# 12S.net
KiCad netlist of a schematic drawn in EAGLE
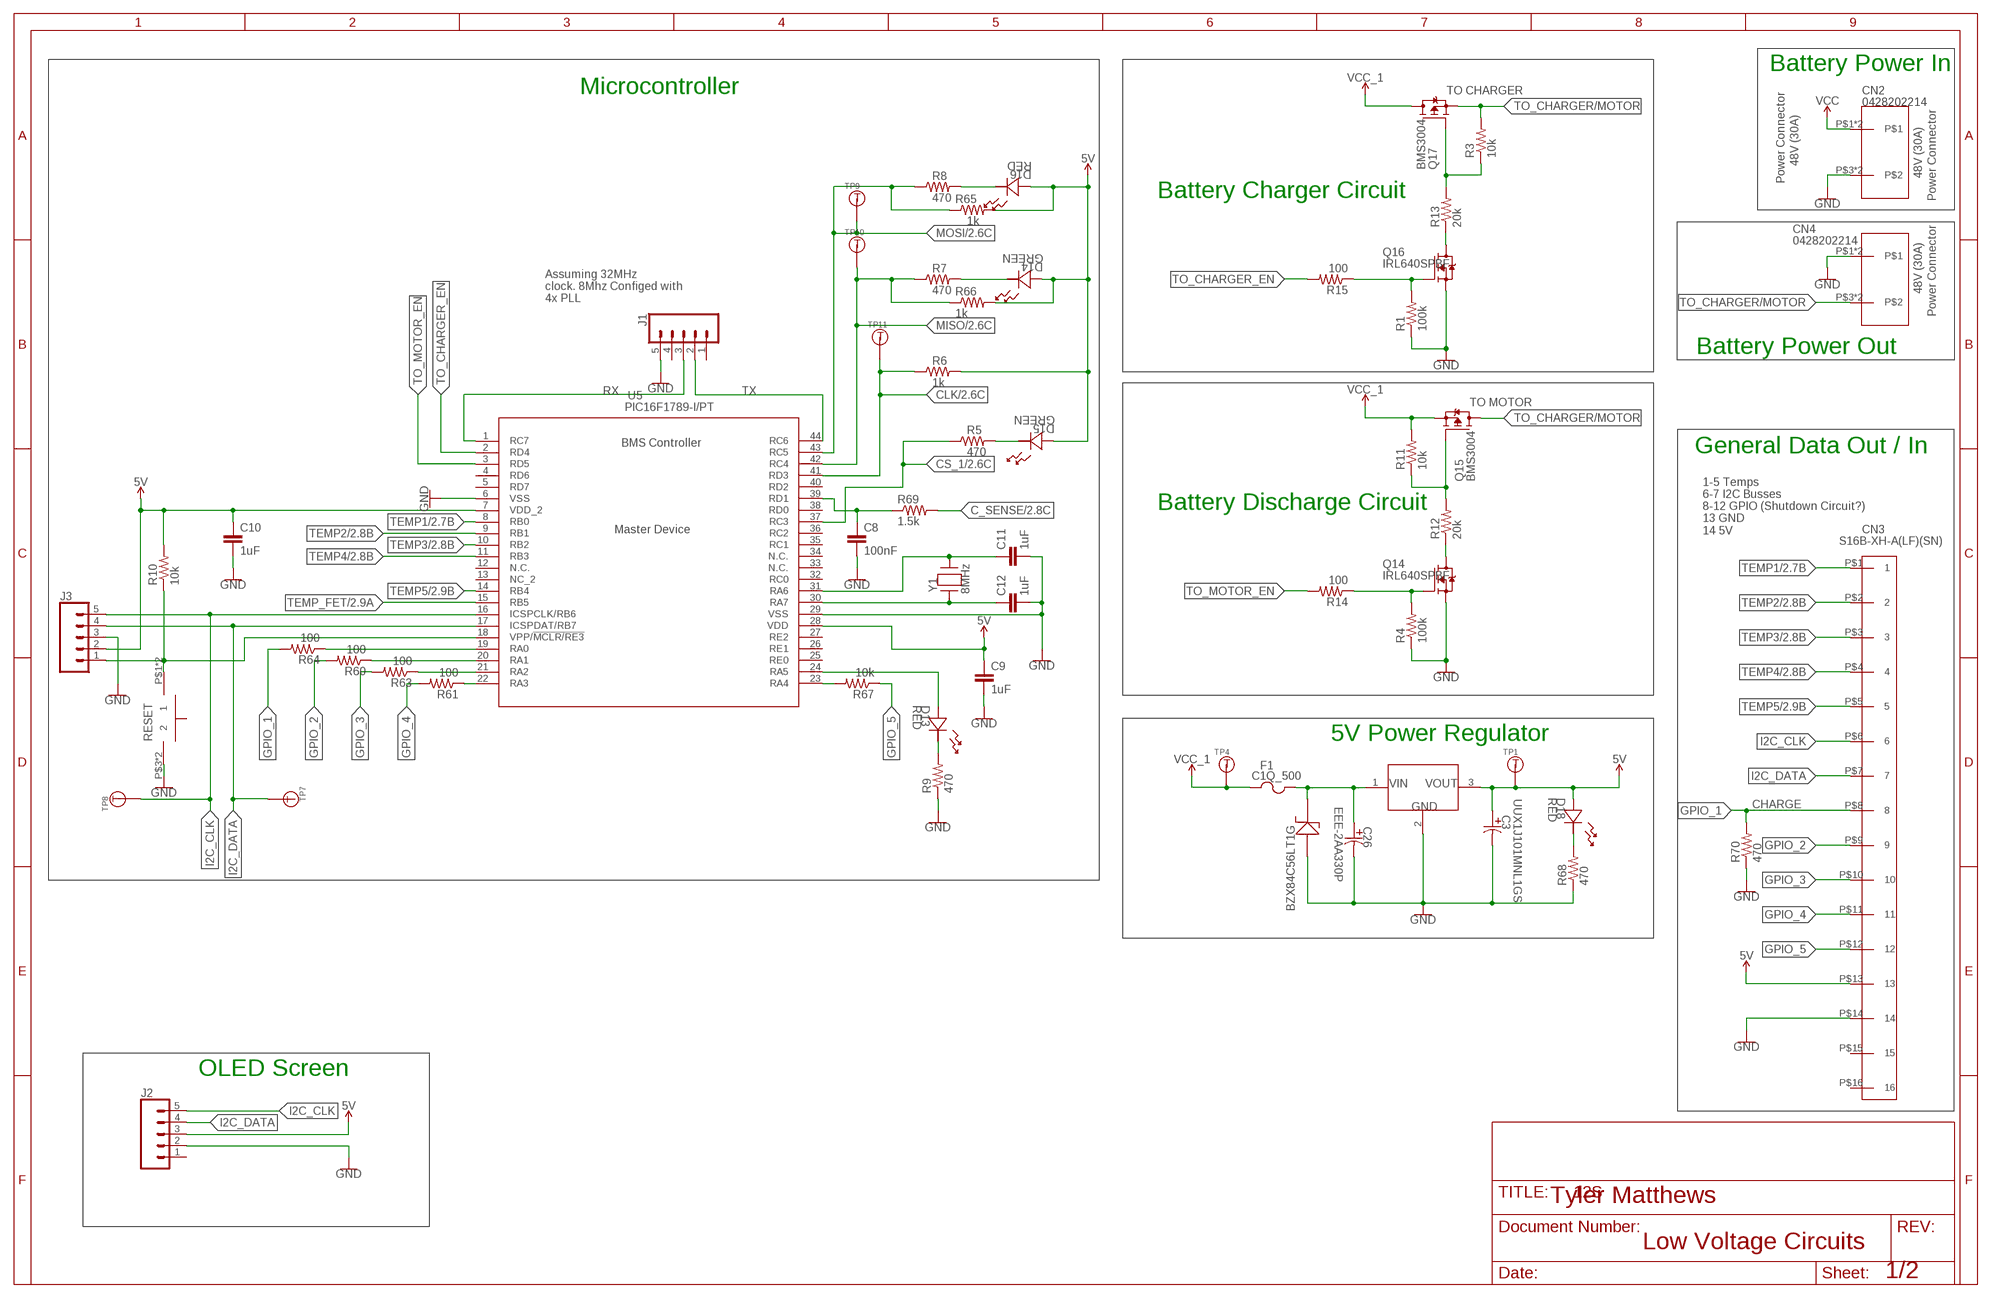
[diagram p0: schematic, sheet 1]
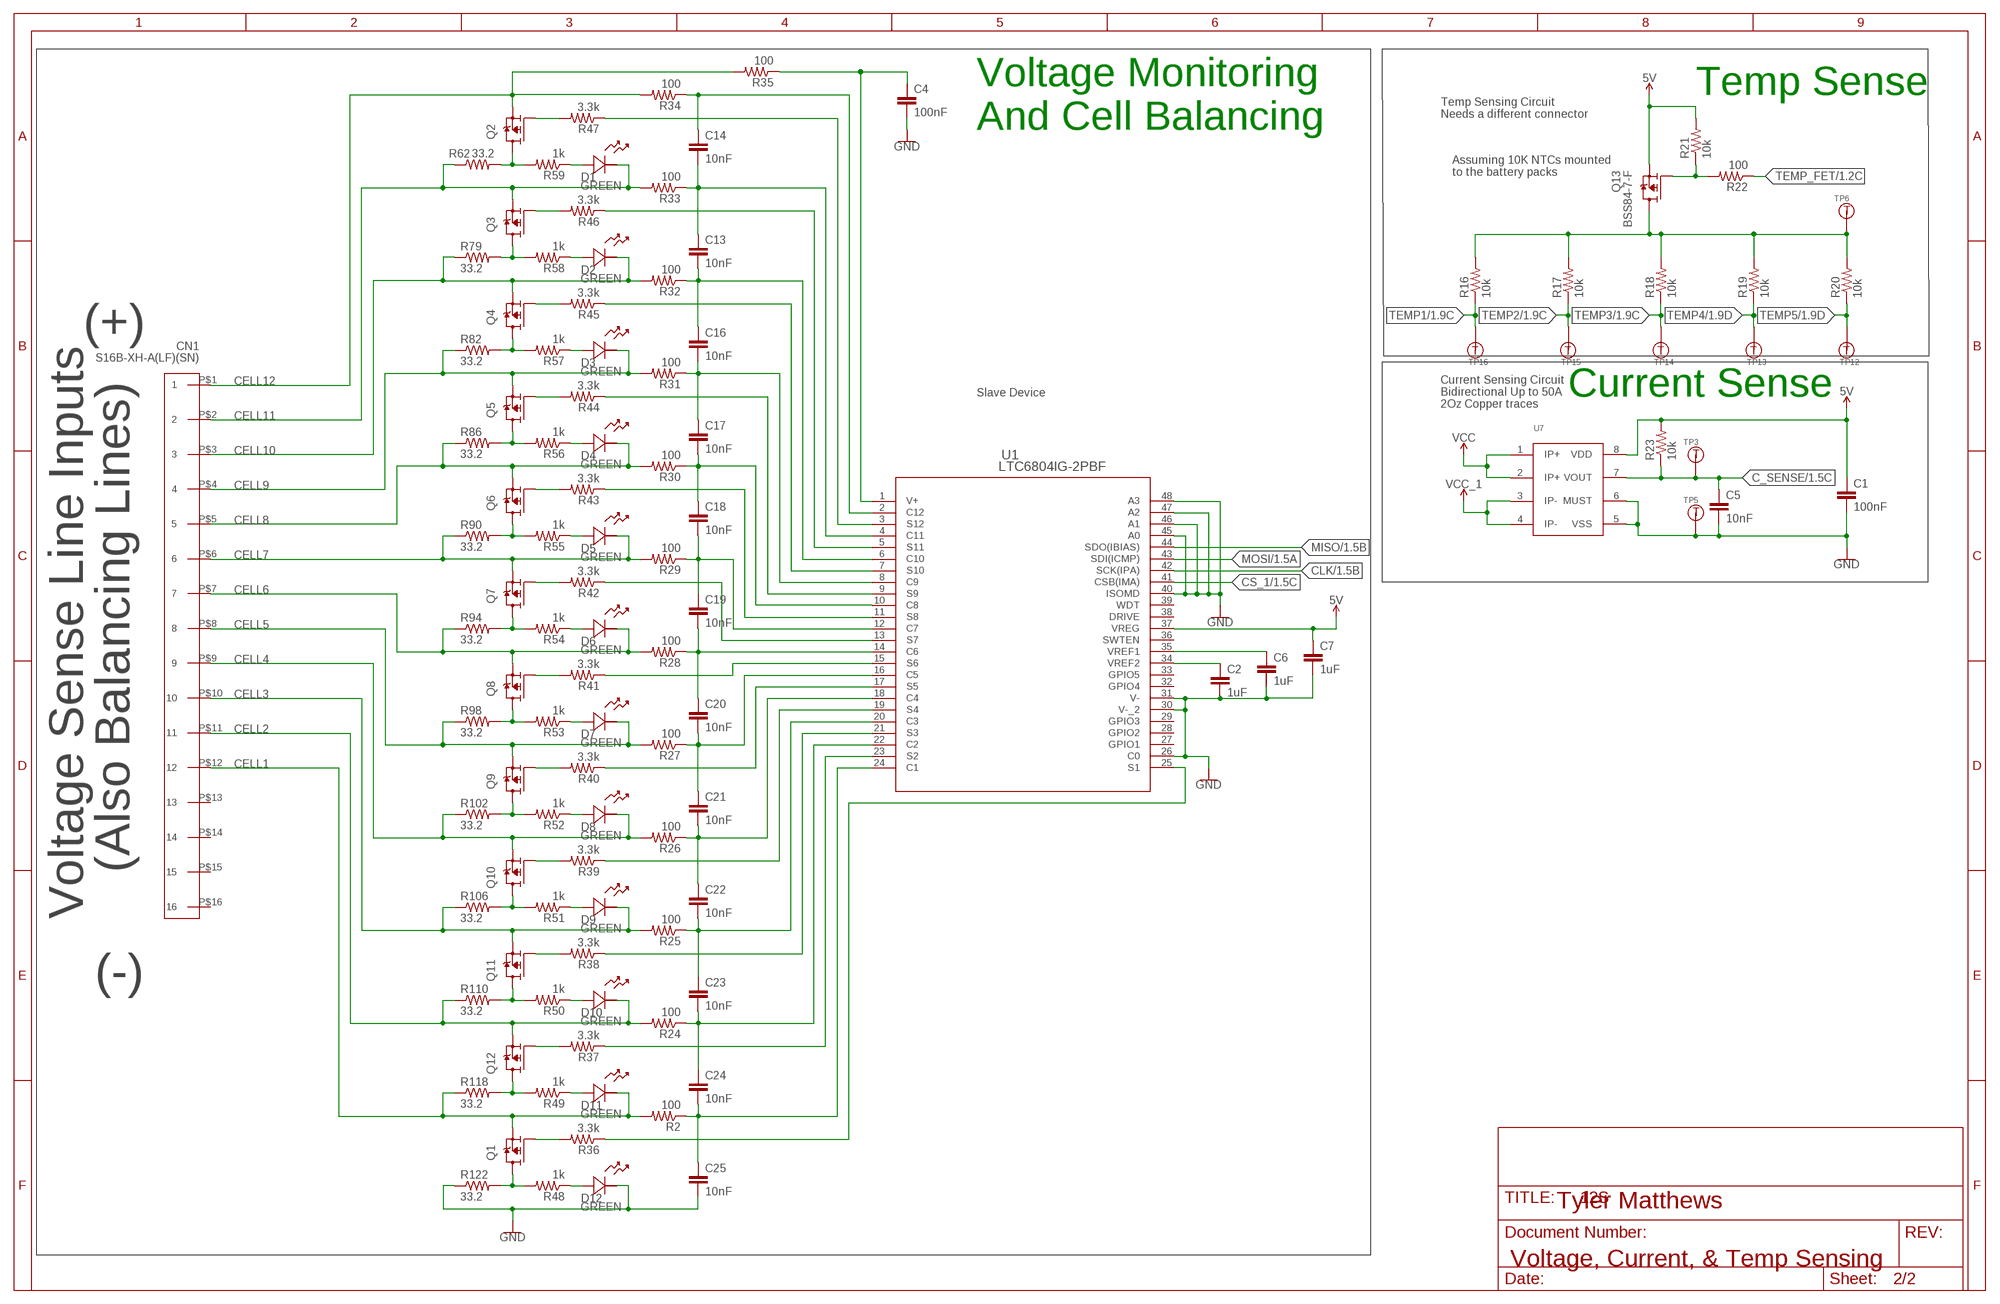
[diagram p1: schematic, sheet 2]

(export (version "E")
  (design (tool "Eeschema 10.0.6"))
  (components
    (comp (ref "C1")
      (value "100nF")
      (footprint "eagle-import:C0603")
      (libsource (lib "eagle-import") (part "C-EUC0603"))
    )
    (comp (ref "C2")
      (value "1uF")
      (footprint "eagle-import:C0603")
      (libsource (lib "eagle-import") (part "C-EUC0603"))
    )
    (comp (ref "C4")
      (value "100nF")
      (footprint "eagle-import:C0603")
      (libsource (lib "eagle-import") (part "C-EUC0603"))
    )
    (comp (ref "C5")
      (value "10nF")
      (footprint "eagle-import:C0603")
      (libsource (lib "eagle-import") (part "C-EUC0603"))
    )
    (comp (ref "C6")
      (value "1uF")
      (footprint "eagle-import:C0603")
      (libsource (lib "eagle-import") (part "C-EUC0603"))
    )
    (comp (ref "C7")
      (value "1uF")
      (footprint "eagle-import:C0603")
      (libsource (lib "eagle-import") (part "C-EUC0603"))
    )
    (comp (ref "C13")
      (value "10nF")
      (footprint "eagle-import:C0603")
      (libsource (lib "eagle-import") (part "C-EUC0603"))
    )
    (comp (ref "C14")
      (value "10nF")
      (footprint "eagle-import:C0603")
      (libsource (lib "eagle-import") (part "C-EUC0603"))
    )
    (comp (ref "C16")
      (value "10nF")
      (footprint "eagle-import:C0603")
      (libsource (lib "eagle-import") (part "C-EUC0603"))
    )
    (comp (ref "C17")
      (value "10nF")
      (footprint "eagle-import:C0603")
      (libsource (lib "eagle-import") (part "C-EUC0603"))
    )
    (comp (ref "C18")
      (value "10nF")
      (footprint "eagle-import:C0603")
      (libsource (lib "eagle-import") (part "C-EUC0603"))
    )
    (comp (ref "C19")
      (value "10nF")
      (footprint "eagle-import:C0603")
      (libsource (lib "eagle-import") (part "C-EUC0603"))
    )
    (comp (ref "C20")
      (value "10nF")
      (footprint "eagle-import:C0603")
      (libsource (lib "eagle-import") (part "C-EUC0603"))
    )
    (comp (ref "C21")
      (value "10nF")
      (footprint "eagle-import:C0603")
      (libsource (lib "eagle-import") (part "C-EUC0603"))
    )
    (comp (ref "C22")
      (value "10nF")
      (footprint "eagle-import:C0603")
      (libsource (lib "eagle-import") (part "C-EUC0603"))
    )
    (comp (ref "C23")
      (value "10nF")
      (footprint "eagle-import:C0603")
      (libsource (lib "eagle-import") (part "C-EUC0603"))
    )
    (comp (ref "C24")
      (value "10nF")
      (footprint "eagle-import:C0603")
      (libsource (lib "eagle-import") (part "C-EUC0603"))
    )
    (comp (ref "C25")
      (value "10nF")
      (footprint "eagle-import:C0603")
      (libsource (lib "eagle-import") (part "C-EUC0603"))
    )
    (comp (ref "CN1")
      (value "S16B-XH-A(LF)(SN)")
      (footprint "eagle-import:S16B-XH-A(LF)(SN)")
      (libsource (lib "eagle-import") (part "S16B-XH-A(LF)(SN)"))
    )
    (comp (ref "D1")
      (value "GREEN")
      (footprint "eagle-import:LED_DIALIGHT_598")
      (fields (field (name "MANUFACTURER_PART_NUMBER") "5988070107F"))
      (libsource (lib "eagle-import") (part "LED0603"))
    )
    (comp (ref "D2")
      (value "GREEN")
      (footprint "eagle-import:LED_DIALIGHT_598")
      (fields (field (name "MANUFACTURER_PART_NUMBER") "5988070107F"))
      (libsource (lib "eagle-import") (part "LED0603"))
    )
    (comp (ref "D3")
      (value "GREEN")
      (footprint "eagle-import:LED_DIALIGHT_598")
      (fields (field (name "MANUFACTURER_PART_NUMBER") "5988070107F"))
      (libsource (lib "eagle-import") (part "LED0603"))
    )
    (comp (ref "D4")
      (value "GREEN")
      (footprint "eagle-import:LED_DIALIGHT_598")
      (fields (field (name "MANUFACTURER_PART_NUMBER") "5988070107F"))
      (libsource (lib "eagle-import") (part "LED0603"))
    )
    (comp (ref "D5")
      (value "GREEN")
      (footprint "eagle-import:LED_DIALIGHT_598")
      (fields (field (name "MANUFACTURER_PART_NUMBER") "5988070107F"))
      (libsource (lib "eagle-import") (part "LED0603"))
    )
    (comp (ref "D6")
      (value "GREEN")
      (footprint "eagle-import:LED_DIALIGHT_598")
      (fields (field (name "MANUFACTURER_PART_NUMBER") "5988070107F"))
      (libsource (lib "eagle-import") (part "LED0603"))
    )
    (comp (ref "D7")
      (value "GREEN")
      (footprint "eagle-import:LED_DIALIGHT_598")
      (fields (field (name "MANUFACTURER_PART_NUMBER") "5988070107F"))
      (libsource (lib "eagle-import") (part "LED0603"))
    )
    (comp (ref "D8")
      (value "GREEN")
      (footprint "eagle-import:LED_DIALIGHT_598")
      (fields (field (name "MANUFACTURER_PART_NUMBER") "5988070107F"))
      (libsource (lib "eagle-import") (part "LED0603"))
    )
    (comp (ref "D9")
      (value "GREEN")
      (footprint "eagle-import:LED_DIALIGHT_598")
      (fields (field (name "MANUFACTURER_PART_NUMBER") "5988070107F"))
      (libsource (lib "eagle-import") (part "LED0603"))
    )
    (comp (ref "D10")
      (value "GREEN")
      (footprint "eagle-import:LED_DIALIGHT_598")
      (fields (field (name "MANUFACTURER_PART_NUMBER") "5988070107F"))
      (libsource (lib "eagle-import") (part "LED0603"))
    )
    (comp (ref "D11")
      (value "GREEN")
      (footprint "eagle-import:LED_DIALIGHT_598")
      (fields (field (name "MANUFACTURER_PART_NUMBER") "5988070107F"))
      (libsource (lib "eagle-import") (part "LED0603"))
    )
    (comp (ref "D12")
      (value "GREEN")
      (footprint "eagle-import:LED_DIALIGHT_598")
      (fields (field (name "MANUFACTURER_PART_NUMBER") "5988070107F"))
      (libsource (lib "eagle-import") (part "LED0603"))
    )
    (comp (ref "Q1")
      (value "BSS308PEH6327XTSA1")
      (footprint "eagle-import:BSS308PEH6327XTSA1")
      (libsource (lib "eagle-import") (part "BSS308PEH6327XTSA1"))
    )
    (comp (ref "Q2")
      (value "BSS308PEH6327XTSA1")
      (footprint "eagle-import:BSS308PEH6327XTSA1")
      (libsource (lib "eagle-import") (part "BSS308PEH6327XTSA1"))
    )
    (comp (ref "Q3")
      (value "BSS308PEH6327XTSA1")
      (footprint "eagle-import:BSS308PEH6327XTSA1")
      (libsource (lib "eagle-import") (part "BSS308PEH6327XTSA1"))
    )
    (comp (ref "Q4")
      (value "BSS308PEH6327XTSA1")
      (footprint "eagle-import:BSS308PEH6327XTSA1")
      (libsource (lib "eagle-import") (part "BSS308PEH6327XTSA1"))
    )
    (comp (ref "Q5")
      (value "BSS308PEH6327XTSA1")
      (footprint "eagle-import:BSS308PEH6327XTSA1")
      (libsource (lib "eagle-import") (part "BSS308PEH6327XTSA1"))
    )
    (comp (ref "Q6")
      (value "BSS308PEH6327XTSA1")
      (footprint "eagle-import:BSS308PEH6327XTSA1")
      (libsource (lib "eagle-import") (part "BSS308PEH6327XTSA1"))
    )
    (comp (ref "Q7")
      (value "BSS308PEH6327XTSA1")
      (footprint "eagle-import:BSS308PEH6327XTSA1")
      (libsource (lib "eagle-import") (part "BSS308PEH6327XTSA1"))
    )
    (comp (ref "Q8")
      (value "BSS308PEH6327XTSA1")
      (footprint "eagle-import:BSS308PEH6327XTSA1")
      (libsource (lib "eagle-import") (part "BSS308PEH6327XTSA1"))
    )
    (comp (ref "Q9")
      (value "BSS308PEH6327XTSA1")
      (footprint "eagle-import:BSS308PEH6327XTSA1")
      (libsource (lib "eagle-import") (part "BSS308PEH6327XTSA1"))
    )
    (comp (ref "Q10")
      (value "BSS308PEH6327XTSA1")
      (footprint "eagle-import:BSS308PEH6327XTSA1")
      (libsource (lib "eagle-import") (part "BSS308PEH6327XTSA1"))
    )
    (comp (ref "Q11")
      (value "BSS308PEH6327XTSA1")
      (footprint "eagle-import:BSS308PEH6327XTSA1")
      (libsource (lib "eagle-import") (part "BSS308PEH6327XTSA1"))
    )
    (comp (ref "Q12")
      (value "BSS308PEH6327XTSA1")
      (footprint "eagle-import:BSS308PEH6327XTSA1")
      (libsource (lib "eagle-import") (part "BSS308PEH6327XTSA1"))
    )
    (comp (ref "Q13")
      (value "BSS84-7-F")
      (footprint "eagle-import:SOT-23")
      (fields (field (name "MANUFACTURER_PART_NUMBER") "BSS847F"))
      (libsource (lib "eagle-import") (part "BSS84-7-F"))
    )
    (comp (ref "R2")
      (value "100")
      (footprint "eagle-import:R0603")
      (libsource (lib "eagle-import") (part "R-US_R0603"))
    )
    (comp (ref "R16")
      (value "10k")
      (footprint "eagle-import:R0603")
      (libsource (lib "eagle-import") (part "R-US_R0603"))
    )
    (comp (ref "R17")
      (value "10k")
      (footprint "eagle-import:R0603")
      (libsource (lib "eagle-import") (part "R-US_R0603"))
    )
    (comp (ref "R18")
      (value "10k")
      (footprint "eagle-import:R0603")
      (libsource (lib "eagle-import") (part "R-US_R0603"))
    )
    (comp (ref "R19")
      (value "10k")
      (footprint "eagle-import:R0603")
      (libsource (lib "eagle-import") (part "R-US_R0603"))
    )
    (comp (ref "R20")
      (value "10k")
      (footprint "eagle-import:R0603")
      (libsource (lib "eagle-import") (part "R-US_R0603"))
    )
    (comp (ref "R21")
      (value "10k")
      (footprint "eagle-import:R0603")
      (libsource (lib "eagle-import") (part "R-US_R0603"))
    )
    (comp (ref "R22")
      (value "100")
      (footprint "eagle-import:R0603")
      (libsource (lib "eagle-import") (part "R-US_R0603"))
    )
    (comp (ref "R23")
      (value "10k")
      (footprint "eagle-import:R0603")
      (libsource (lib "eagle-import") (part "R-US_R0603"))
    )
    (comp (ref "R24")
      (value "100")
      (footprint "eagle-import:R0603")
      (libsource (lib "eagle-import") (part "R-US_R0603"))
    )
    (comp (ref "R25")
      (value "100")
      (footprint "eagle-import:R0603")
      (libsource (lib "eagle-import") (part "R-US_R0603"))
    )
    (comp (ref "R26")
      (value "100")
      (footprint "eagle-import:R0603")
      (libsource (lib "eagle-import") (part "R-US_R0603"))
    )
    (comp (ref "R27")
      (value "100")
      (footprint "eagle-import:R0603")
      (libsource (lib "eagle-import") (part "R-US_R0603"))
    )
    (comp (ref "R28")
      (value "100")
      (footprint "eagle-import:R0603")
      (libsource (lib "eagle-import") (part "R-US_R0603"))
    )
    (comp (ref "R29")
      (value "100")
      (footprint "eagle-import:R0603")
      (libsource (lib "eagle-import") (part "R-US_R0603"))
    )
    (comp (ref "R30")
      (value "100")
      (footprint "eagle-import:R0603")
      (libsource (lib "eagle-import") (part "R-US_R0603"))
    )
    (comp (ref "R31")
      (value "100")
      (footprint "eagle-import:R0603")
      (libsource (lib "eagle-import") (part "R-US_R0603"))
    )
    (comp (ref "R32")
      (value "100")
      (footprint "eagle-import:R0603")
      (libsource (lib "eagle-import") (part "R-US_R0603"))
    )
    (comp (ref "R33")
      (value "100")
      (footprint "eagle-import:R0603")
      (libsource (lib "eagle-import") (part "R-US_R0603"))
    )
    (comp (ref "R34")
      (value "100")
      (footprint "eagle-import:R0603")
      (libsource (lib "eagle-import") (part "R-US_R0603"))
    )
    (comp (ref "R35")
      (value "100")
      (footprint "eagle-import:R0603")
      (libsource (lib "eagle-import") (part "R-US_R0603"))
    )
    (comp (ref "R36")
      (value "3.3k")
      (footprint "eagle-import:R0603")
      (libsource (lib "eagle-import") (part "R-US_R0603"))
    )
    (comp (ref "R37")
      (value "3.3k")
      (footprint "eagle-import:R0603")
      (libsource (lib "eagle-import") (part "R-US_R0603"))
    )
    (comp (ref "R38")
      (value "3.3k")
      (footprint "eagle-import:R0603")
      (libsource (lib "eagle-import") (part "R-US_R0603"))
    )
    (comp (ref "R39")
      (value "3.3k")
      (footprint "eagle-import:R0603")
      (libsource (lib "eagle-import") (part "R-US_R0603"))
    )
    (comp (ref "R40")
      (value "3.3k")
      (footprint "eagle-import:R0603")
      (libsource (lib "eagle-import") (part "R-US_R0603"))
    )
    (comp (ref "R41")
      (value "3.3k")
      (footprint "eagle-import:R0603")
      (libsource (lib "eagle-import") (part "R-US_R0603"))
    )
    (comp (ref "R42")
      (value "3.3k")
      (footprint "eagle-import:R0603")
      (libsource (lib "eagle-import") (part "R-US_R0603"))
    )
    (comp (ref "R43")
      (value "3.3k")
      (footprint "eagle-import:R0603")
      (libsource (lib "eagle-import") (part "R-US_R0603"))
    )
    (comp (ref "R44")
      (value "3.3k")
      (footprint "eagle-import:R0603")
      (libsource (lib "eagle-import") (part "R-US_R0603"))
    )
    (comp (ref "R45")
      (value "3.3k")
      (footprint "eagle-import:R0603")
      (libsource (lib "eagle-import") (part "R-US_R0603"))
    )
    (comp (ref "R46")
      (value "3.3k")
      (footprint "eagle-import:R0603")
      (libsource (lib "eagle-import") (part "R-US_R0603"))
    )
    (comp (ref "R47")
      (value "3.3k")
      (footprint "eagle-import:R0603")
      (libsource (lib "eagle-import") (part "R-US_R0603"))
    )
    (comp (ref "R48")
      (value "1k")
      (footprint "eagle-import:R0603")
      (libsource (lib "eagle-import") (part "R-US_R0603"))
    )
    (comp (ref "R49")
      (value "1k")
      (footprint "eagle-import:R0603")
      (libsource (lib "eagle-import") (part "R-US_R0603"))
    )
    (comp (ref "R50")
      (value "1k")
      (footprint "eagle-import:R0603")
      (libsource (lib "eagle-import") (part "R-US_R0603"))
    )
    (comp (ref "R51")
      (value "1k")
      (footprint "eagle-import:R0603")
      (libsource (lib "eagle-import") (part "R-US_R0603"))
    )
    (comp (ref "R52")
      (value "1k")
      (footprint "eagle-import:R0603")
      (libsource (lib "eagle-import") (part "R-US_R0603"))
    )
    (comp (ref "R53")
      (value "1k")
      (footprint "eagle-import:R0603")
      (libsource (lib "eagle-import") (part "R-US_R0603"))
    )
    (comp (ref "R54")
      (value "1k")
      (footprint "eagle-import:R0603")
      (libsource (lib "eagle-import") (part "R-US_R0603"))
    )
    (comp (ref "R55")
      (value "1k")
      (footprint "eagle-import:R0603")
      (libsource (lib "eagle-import") (part "R-US_R0603"))
    )
    (comp (ref "R56")
      (value "1k")
      (footprint "eagle-import:R0603")
      (libsource (lib "eagle-import") (part "R-US_R0603"))
    )
    (comp (ref "R57")
      (value "1k")
      (footprint "eagle-import:R0603")
      (libsource (lib "eagle-import") (part "R-US_R0603"))
    )
    (comp (ref "R58")
      (value "1k")
      (footprint "eagle-import:R0603")
      (libsource (lib "eagle-import") (part "R-US_R0603"))
    )
    (comp (ref "R59")
      (value "1k")
      (footprint "eagle-import:R0603")
      (libsource (lib "eagle-import") (part "R-US_R0603"))
    )
    (comp (ref "R62")
      (value "33.2")
      (footprint "eagle-import:R0805")
      (libsource (lib "eagle-import") (part "R-US_R0805"))
    )
    (comp (ref "R79")
      (value "33.2")
      (footprint "eagle-import:R0805")
      (libsource (lib "eagle-import") (part "R-US_R0805"))
    )
    (comp (ref "R82")
      (value "33.2")
      (footprint "eagle-import:R0805")
      (libsource (lib "eagle-import") (part "R-US_R0805"))
    )
    (comp (ref "R86")
      (value "33.2")
      (footprint "eagle-import:R0805")
      (libsource (lib "eagle-import") (part "R-US_R0805"))
    )
    (comp (ref "R90")
      (value "33.2")
      (footprint "eagle-import:R0805")
      (libsource (lib "eagle-import") (part "R-US_R0805"))
    )
    (comp (ref "R94")
      (value "33.2")
      (footprint "eagle-import:R0805")
      (libsource (lib "eagle-import") (part "R-US_R0805"))
    )
    (comp (ref "R98")
      (value "33.2")
      (footprint "eagle-import:R0805")
      (libsource (lib "eagle-import") (part "R-US_R0805"))
    )
    (comp (ref "R102")
      (value "33.2")
      (footprint "eagle-import:R0805")
      (libsource (lib "eagle-import") (part "R-US_R0805"))
    )
    (comp (ref "R106")
      (value "33.2")
      (footprint "eagle-import:R0805")
      (libsource (lib "eagle-import") (part "R-US_R0805"))
    )
    (comp (ref "R110")
      (value "33.2")
      (footprint "eagle-import:R0805")
      (libsource (lib "eagle-import") (part "R-US_R0805"))
    )
    (comp (ref "R118")
      (value "33.2")
      (footprint "eagle-import:R0805")
      (libsource (lib "eagle-import") (part "R-US_R0805"))
    )
    (comp (ref "R122")
      (value "33.2")
      (footprint "eagle-import:R0805")
      (libsource (lib "eagle-import") (part "R-US_R0805"))
    )
    (comp (ref "TP3")
      (value "TP5015")
      (footprint "eagle-import:TP5015")
      (fields (field (name "MANUFACTURER_PART_NUMBER") "5015"))
      (libsource (lib "eagle-import") (part "TP5015"))
    )
    (comp (ref "TP5")
      (value "TP5015")
      (footprint "eagle-import:TP5015")
      (fields (field (name "MANUFACTURER_PART_NUMBER") "5015"))
      (libsource (lib "eagle-import") (part "TP5015"))
    )
    (comp (ref "TP6")
      (value "TP5015")
      (footprint "eagle-import:TP5015")
      (fields (field (name "MANUFACTURER_PART_NUMBER") "5015"))
      (libsource (lib "eagle-import") (part "TP5015"))
    )
    (comp (ref "TP12")
      (value "TP5015")
      (footprint "eagle-import:TP5015")
      (fields (field (name "MANUFACTURER_PART_NUMBER") "5015"))
      (libsource (lib "eagle-import") (part "TP5015"))
    )
    (comp (ref "TP13")
      (value "TP5015")
      (footprint "eagle-import:TP5015")
      (fields (field (name "MANUFACTURER_PART_NUMBER") "5015"))
      (libsource (lib "eagle-import") (part "TP5015"))
    )
    (comp (ref "TP14")
      (value "TP5015")
      (footprint "eagle-import:TP5015")
      (fields (field (name "MANUFACTURER_PART_NUMBER") "5015"))
      (libsource (lib "eagle-import") (part "TP5015"))
    )
    (comp (ref "TP15")
      (value "TP5015")
      (footprint "eagle-import:TP5015")
      (fields (field (name "MANUFACTURER_PART_NUMBER") "5015"))
      (libsource (lib "eagle-import") (part "TP5015"))
    )
    (comp (ref "TP16")
      (value "TP5015")
      (footprint "eagle-import:TP5015")
      (fields (field (name "MANUFACTURER_PART_NUMBER") "5015"))
      (libsource (lib "eagle-import") (part "TP5015"))
    )
    (comp (ref "U1")
      (value "LTC6804IG-2PBF")
      (footprint "eagle-import:SSOP-48_G")
      (fields (field (name "MANUFACTURER_PART_NUMBER") "LTC6804HG-2#PBF"))
      (libsource (lib "eagle-import") (part "LTC6804IG-2PBF"))
    )
    (comp (ref "U7")
      (value "MLX91210")
      (footprint "eagle-import:SOIC-8")
      (fields (field (name "MANUFACTURER_PART_NUMBER") "MLX91210KDC-CAS-102-SP"))
      (libsource (lib "eagle-import") (part "MLX91210"))
    )
    (comp (ref "C3")
      (value "UUX1J101MNL1GS")
      (footprint "eagle-import:PCAP_10X10-ELECT")
      (libsource (lib "eagle-import") (part "UUX1J101MNL1GS"))
    )
    (comp (ref "C8")
      (value "100nF")
      (footprint "eagle-import:C0603")
      (libsource (lib "eagle-import") (part "C-EUC0603"))
    )
    (comp (ref "C9")
      (value "1uF")
      (footprint "eagle-import:C0603")
      (libsource (lib "eagle-import") (part "C-EUC0603"))
    )
    (comp (ref "C10")
      (value "1uF")
      (footprint "eagle-import:C0603")
      (libsource (lib "eagle-import") (part "C-EUC0603"))
    )
    (comp (ref "C11")
      (value "1uF")
      (footprint "eagle-import:C0603")
      (libsource (lib "eagle-import") (part "C-EUC0603"))
    )
    (comp (ref "C12")
      (value "1uF")
      (footprint "eagle-import:C0603")
      (libsource (lib "eagle-import") (part "C-EUC0603"))
    )
    (comp (ref "C26")
      (value "EEE-2AA330P")
      (footprint "eagle-import:CAP_EEE_G")
      (fields (field (name "MANUFACTURER_PART_NUMBER") "EEE2AA330P"))
      (libsource (lib "eagle-import") (part "EEE-2AA330P"))
    )
    (comp (ref "CN2")
      (value "0428202214")
      (footprint "eagle-import:0428202214")
      (libsource (lib "eagle-import") (part "0428202214"))
    )
    (comp (ref "CN3")
      (value "S16B-XH-A(LF)(SN)")
      (footprint "eagle-import:S16B-XH-A(LF)(SN)")
      (libsource (lib "eagle-import") (part "S16B-XH-A(LF)(SN)"))
    )
    (comp (ref "CN4")
      (value "0428202214")
      (footprint "eagle-import:0428202214")
      (libsource (lib "eagle-import") (part "0428202214"))
    )
    (comp (ref "D13")
      (value "RED")
      (footprint "eagle-import:LED_DIALIGHT_598")
      (fields (field (name "MANUFACTURER_PART_NUMBER") "5988070107F"))
      (libsource (lib "eagle-import") (part "LED0603"))
    )
    (comp (ref "D14")
      (value "GREEN")
      (footprint "eagle-import:LED_DIALIGHT_598")
      (fields (field (name "MANUFACTURER_PART_NUMBER") "5988070107F"))
      (libsource (lib "eagle-import") (part "LED0603"))
    )
    (comp (ref "D15")
      (value "GREEN")
      (footprint "eagle-import:LED_DIALIGHT_598")
      (fields (field (name "MANUFACTURER_PART_NUMBER") "5988070107F"))
      (libsource (lib "eagle-import") (part "LED0603"))
    )
    (comp (ref "D16")
      (value "RED")
      (footprint "eagle-import:LED_DIALIGHT_598")
      (fields (field (name "MANUFACTURER_PART_NUMBER") "5988070107F"))
      (libsource (lib "eagle-import") (part "LED0603"))
    )
    (comp (ref "D17")
      (value "BZX84C56LT1G")
      (footprint "eagle-import:SOT-23")
      (libsource (lib "eagle-import") (part "BZX84C56LT1G"))
    )
    (comp (ref "D18")
      (value "RED")
      (footprint "eagle-import:LED_DIALIGHT_598")
      (fields (field (name "MANUFACTURER_PART_NUMBER") "5988070107F"))
      (libsource (lib "eagle-import") (part "LED0603"))
    )
    (comp (ref "F1")
      (value "C1Q_500")
      (footprint "eagle-import:C1")
      (fields (field (name "MANUFACTURER_PART_NUMBER") "C1Q 500"))
      (libsource (lib "eagle-import") (part "C1Q_500"))
    )
    (comp (ref "J1")
      (value "CONN_05")
      (footprint "eagle-import:1X05")
      (fields (field (name "MANUFACTURER_PART_NUMBER") "M20-9990546"))
      (libsource (lib "eagle-import") (part "CONN_05"))
    )
    (comp (ref "J2")
      (value "CONN_05")
      (footprint "eagle-import:1X05")
      (fields (field (name "MANUFACTURER_PART_NUMBER") "M20-9990546"))
      (libsource (lib "eagle-import") (part "CONN_05"))
    )
    (comp (ref "J3")
      (value "CONN_05")
      (footprint "eagle-import:1X05")
      (fields (field (name "MANUFACTURER_PART_NUMBER") "M20-9990546"))
      (libsource (lib "eagle-import") (part "CONN_05"))
    )
    (comp (ref "Q14")
      (value "IRL640SPBF")
      (footprint "eagle-import:D2PAK")
      (libsource (lib "eagle-import") (part "IRL640SPBF"))
    )
    (comp (ref "Q15")
      (value "BMS3004")
      (footprint "eagle-import:TO-220")
      (fields (field (name "MANUFACTURER_PART_NUMBER") "BMS3004-1E"))
      (libsource (lib "eagle-import") (part "BMS3004"))
    )
    (comp (ref "Q16")
      (value "IRL640SPBF")
      (footprint "eagle-import:D2PAK")
      (libsource (lib "eagle-import") (part "IRL640SPBF"))
    )
    (comp (ref "Q17")
      (value "BMS3004")
      (footprint "eagle-import:TO-220")
      (fields (field (name "MANUFACTURER_PART_NUMBER") "BMS3004-1E"))
      (libsource (lib "eagle-import") (part "BMS3004"))
    )
    (comp (ref "R1")
      (value "100k")
      (footprint "eagle-import:R0603")
      (libsource (lib "eagle-import") (part "R-US_R0603"))
    )
    (comp (ref "R3")
      (value "10k")
      (footprint "eagle-import:R0603")
      (libsource (lib "eagle-import") (part "R-US_R0603"))
    )
    (comp (ref "R4")
      (value "100k")
      (footprint "eagle-import:R0603")
      (libsource (lib "eagle-import") (part "R-US_R0603"))
    )
    (comp (ref "R5")
      (value "470")
      (footprint "eagle-import:R0603")
      (libsource (lib "eagle-import") (part "R-US_R0603"))
    )
    (comp (ref "R6")
      (value "1k")
      (footprint "eagle-import:R0603")
      (libsource (lib "eagle-import") (part "R-US_R0603"))
    )
    (comp (ref "R7")
      (value "470")
      (footprint "eagle-import:R0603")
      (libsource (lib "eagle-import") (part "R-US_R0603"))
    )
    (comp (ref "R8")
      (value "470")
      (footprint "eagle-import:R0603")
      (libsource (lib "eagle-import") (part "R-US_R0603"))
    )
    (comp (ref "R9")
      (value "470")
      (footprint "eagle-import:R0603")
      (libsource (lib "eagle-import") (part "R-US_R0603"))
    )
    (comp (ref "R10")
      (value "10k")
      (footprint "eagle-import:R0603")
      (libsource (lib "eagle-import") (part "R-US_R0603"))
    )
    (comp (ref "R11")
      (value "10k")
      (footprint "eagle-import:R0603")
      (libsource (lib "eagle-import") (part "R-US_R0603"))
    )
    (comp (ref "R12")
      (value "20k")
      (footprint "eagle-import:R0603")
      (libsource (lib "eagle-import") (part "R-US_R0603"))
    )
    (comp (ref "R13")
      (value "20k")
      (footprint "eagle-import:R0603")
      (libsource (lib "eagle-import") (part "R-US_R0603"))
    )
    (comp (ref "R14")
      (value "100")
      (footprint "eagle-import:R0603")
      (libsource (lib "eagle-import") (part "R-US_R0603"))
    )
    (comp (ref "R15")
      (value "100")
      (footprint "eagle-import:R0603")
      (libsource (lib "eagle-import") (part "R-US_R0603"))
    )
    (comp (ref "R60")
      (value "100")
      (footprint "eagle-import:R0603")
      (libsource (lib "eagle-import") (part "R-US_R0603"))
    )
    (comp (ref "R61")
      (value "100")
      (footprint "eagle-import:R0603")
      (libsource (lib "eagle-import") (part "R-US_R0603"))
    )
    (comp (ref "R63")
      (value "100")
      (footprint "eagle-import:R0603")
      (libsource (lib "eagle-import") (part "R-US_R0603"))
    )
    (comp (ref "R64")
      (value "100")
      (footprint "eagle-import:R0603")
      (libsource (lib "eagle-import") (part "R-US_R0603"))
    )
    (comp (ref "R65")
      (value "1k")
      (footprint "eagle-import:R0603")
      (libsource (lib "eagle-import") (part "R-US_R0603"))
    )
    (comp (ref "R66")
      (value "1k")
      (footprint "eagle-import:R0603")
      (libsource (lib "eagle-import") (part "R-US_R0603"))
    )
    (comp (ref "R67")
      (value "10k")
      (footprint "eagle-import:R0603")
      (libsource (lib "eagle-import") (part "R-US_R0603"))
    )
    (comp (ref "R68")
      (value "470")
      (footprint "eagle-import:R0603")
      (libsource (lib "eagle-import") (part "R-US_R0603"))
    )
    (comp (ref "R69")
      (value "1.5k")
      (footprint "eagle-import:R0603")
      (libsource (lib "eagle-import") (part "R-US_R0603"))
    )
    (comp (ref "R70")
      (value "470")
      (footprint "eagle-import:R0603")
      (libsource (lib "eagle-import") (part "R-US_R0603"))
    )
    (comp (ref "S2")
      (value "TL3305AF260QG")
      (footprint "eagle-import:TL3305AF260QG")
      (libsource (lib "eagle-import") (part "TL3305AF260QG"))
    )
    (comp (ref "TP1")
      (value "TP5015")
      (footprint "eagle-import:TP5015")
      (fields (field (name "MANUFACTURER_PART_NUMBER") "5015"))
      (libsource (lib "eagle-import") (part "TP5015"))
    )
    (comp (ref "TP4")
      (value "TP5015")
      (footprint "eagle-import:TP5015")
      (fields (field (name "MANUFACTURER_PART_NUMBER") "5015"))
      (libsource (lib "eagle-import") (part "TP5015"))
    )
    (comp (ref "TP7")
      (value "TP5015")
      (footprint "eagle-import:TP5015")
      (fields (field (name "MANUFACTURER_PART_NUMBER") "5015"))
      (libsource (lib "eagle-import") (part "TP5015"))
    )
    (comp (ref "TP8")
      (value "TP5015")
      (footprint "eagle-import:TP5015")
      (fields (field (name "MANUFACTURER_PART_NUMBER") "5015"))
      (libsource (lib "eagle-import") (part "TP5015"))
    )
    (comp (ref "TP9")
      (value "TP5015")
      (footprint "eagle-import:TP5015")
      (fields (field (name "MANUFACTURER_PART_NUMBER") "5015"))
      (libsource (lib "eagle-import") (part "TP5015"))
    )
    (comp (ref "TP10")
      (value "TP5015")
      (footprint "eagle-import:TP5015")
      (fields (field (name "MANUFACTURER_PART_NUMBER") "5015"))
      (libsource (lib "eagle-import") (part "TP5015"))
    )
    (comp (ref "TP11")
      (value "TP5015")
      (footprint "eagle-import:TP5015")
      (fields (field (name "MANUFACTURER_PART_NUMBER") "5015"))
      (libsource (lib "eagle-import") (part "TP5015"))
    )
    (comp (ref "U3")
      (value "SRH05S05")
      (footprint "eagle-import:SIP3")
      (libsource (lib "eagle-import") (part "SRH05S05"))
    )
    (comp (ref "U5")
      (value "PIC16F1789-I/PT")
      (footprint "eagle-import:TQFP44_MC")
      (fields (field (name "MANUFACTURER_PART_NUMBER") "PIC16F1789T-I/PT"))
      (libsource (lib "eagle-import") (part "PIC16F1789-I/PT"))
    )
    (comp (ref "Y1")
      (value "8MHz")
      (footprint "eagle-import:CRYSTAL_HC49SDLF")
      (fields (field (name "MANUFACTURER_PART_NUMBER") "FC4SDCBMF8.0-T1"))
      (libsource (lib "eagle-import") (part "FOXSDLF/080-20"))
    )
  )
  (nets
    (net (code "1") (name "5V") (class "Default")
      (node (ref "C1") (pin "1") (pinfunction "1_1") (pintype "passive"))
      (node (ref "C10") (pin "1") (pinfunction "1_1") (pintype "passive"))
      (node (ref "C3") (pin "1") (pinfunction "11_1") (pintype "passive"))
      (node (ref "C7") (pin "1") (pinfunction "1_1") (pintype "passive"))
      (node (ref "C9") (pin "1") (pinfunction "1_1") (pintype "passive"))
      (node (ref "CN3") (pin "P$13") (pinfunction "13_P$13") (pintype "bidirectional"))
      (node (ref "D14") (pin "2") (pinfunction "22_2") (pintype "passive"))
      (node (ref "D15") (pin "2") (pinfunction "22_2") (pintype "passive"))
      (node (ref "D16") (pin "2") (pinfunction "22_2") (pintype "passive"))
      (node (ref "D18") (pin "2") (pinfunction "22_2") (pintype "passive"))
      (node (ref "J2") (pin "3") (pinfunction "3_3") (pintype "passive"))
      (node (ref "J3") (pin "2") (pinfunction "2_2") (pintype "passive"))
      (node (ref "Q13") (pin "2") (pinfunction "S_2") (pintype "passive"))
      (node (ref "R10") (pin "2") (pinfunction "2_2") (pintype "passive"))
      (node (ref "R21") (pin "2") (pinfunction "2_2") (pintype "passive"))
      (node (ref "R23") (pin "2") (pinfunction "2_2") (pintype "passive"))
      (node (ref "R6") (pin "2") (pinfunction "2_2") (pintype "passive"))
      (node (ref "R65") (pin "2") (pinfunction "2_2") (pintype "passive"))
      (node (ref "R66") (pin "2") (pinfunction "2_2") (pintype "passive"))
      (node (ref "TP1") (pin "P$1") (pinfunction "P$1_P$1") (pintype "bidirectional"))
      (node (ref "U1") (pin "37") (pinfunction "VREG_37") (pintype "passive"))
      (node (ref "U3") (pin "3") (pinfunction "VOUT_3") (pintype "bidirectional"))
      (node (ref "U5") (pin "28") (pinfunction "VDD_28") (pintype "power_in"))
      (node (ref "U5") (pin "7") (pinfunction "VDD_2_7") (pintype "power_in"))
      (node (ref "U7") (pin "8") (pinfunction "VDD_8") (pintype "bidirectional"))
    )
    (net (code "2") (name "CELL1") (class "Default")
      (node (ref "CN1") (pin "P$12") (pinfunction "12_P$12") (pintype "bidirectional"))
      (node (ref "D11") (pin "1") (pinfunction "11_1") (pintype "passive"))
      (node (ref "Q1") (pin "P$S") (pinfunction "S_P$S") (pintype "passive"))
      (node (ref "R118") (pin "1") (pinfunction "1_1") (pintype "passive"))
      (node (ref "R2") (pin "2") (pinfunction "2_2") (pintype "passive"))
    )
    (net (code "3") (name "CELL2") (class "Default")
      (node (ref "CN1") (pin "P$11") (pinfunction "11_P$11") (pintype "bidirectional"))
      (node (ref "D10") (pin "1") (pinfunction "11_1") (pintype "passive"))
      (node (ref "Q12") (pin "P$S") (pinfunction "S_P$S") (pintype "passive"))
      (node (ref "R110") (pin "1") (pinfunction "1_1") (pintype "passive"))
      (node (ref "R24") (pin "2") (pinfunction "2_2") (pintype "passive"))
    )
    (net (code "4") (name "CELL3") (class "Default")
      (node (ref "CN1") (pin "P$10") (pinfunction "10_P$10") (pintype "bidirectional"))
      (node (ref "D9") (pin "1") (pinfunction "11_1") (pintype "passive"))
      (node (ref "Q11") (pin "P$S") (pinfunction "S_P$S") (pintype "passive"))
      (node (ref "R106") (pin "1") (pinfunction "1_1") (pintype "passive"))
      (node (ref "R25") (pin "2") (pinfunction "2_2") (pintype "passive"))
    )
    (net (code "5") (name "CELL4") (class "Default")
      (node (ref "CN1") (pin "P$9") (pinfunction "9_P$9") (pintype "bidirectional"))
      (node (ref "D8") (pin "1") (pinfunction "11_1") (pintype "passive"))
      (node (ref "Q10") (pin "P$S") (pinfunction "S_P$S") (pintype "passive"))
      (node (ref "R102") (pin "1") (pinfunction "1_1") (pintype "passive"))
      (node (ref "R26") (pin "2") (pinfunction "2_2") (pintype "passive"))
    )
    (net (code "6") (name "CELL5") (class "Default")
      (node (ref "CN1") (pin "P$8") (pinfunction "8_P$8") (pintype "bidirectional"))
      (node (ref "D7") (pin "1") (pinfunction "11_1") (pintype "passive"))
      (node (ref "Q9") (pin "P$S") (pinfunction "S_P$S") (pintype "passive"))
      (node (ref "R27") (pin "2") (pinfunction "2_2") (pintype "passive"))
      (node (ref "R98") (pin "1") (pinfunction "1_1") (pintype "passive"))
    )
    (net (code "7") (name "CELL6") (class "Default")
      (node (ref "CN1") (pin "P$7") (pinfunction "7_P$7") (pintype "bidirectional"))
      (node (ref "D6") (pin "1") (pinfunction "11_1") (pintype "passive"))
      (node (ref "Q8") (pin "P$S") (pinfunction "S_P$S") (pintype "passive"))
      (node (ref "R28") (pin "2") (pinfunction "2_2") (pintype "passive"))
      (node (ref "R94") (pin "1") (pinfunction "1_1") (pintype "passive"))
    )
    (net (code "8") (name "CELL7") (class "Default")
      (node (ref "CN1") (pin "P$6") (pinfunction "6_P$6") (pintype "bidirectional"))
      (node (ref "D5") (pin "1") (pinfunction "11_1") (pintype "passive"))
      (node (ref "Q7") (pin "P$S") (pinfunction "S_P$S") (pintype "passive"))
      (node (ref "R29") (pin "2") (pinfunction "2_2") (pintype "passive"))
      (node (ref "R90") (pin "1") (pinfunction "1_1") (pintype "passive"))
    )
    (net (code "9") (name "CELL8") (class "Default")
      (node (ref "CN1") (pin "P$5") (pinfunction "5_P$5") (pintype "bidirectional"))
      (node (ref "D4") (pin "1") (pinfunction "11_1") (pintype "passive"))
      (node (ref "Q6") (pin "P$S") (pinfunction "S_P$S") (pintype "passive"))
      (node (ref "R30") (pin "2") (pinfunction "2_2") (pintype "passive"))
      (node (ref "R86") (pin "1") (pinfunction "1_1") (pintype "passive"))
    )
    (net (code "10") (name "CELL9") (class "Default")
      (node (ref "CN1") (pin "P$4") (pinfunction "4_P$4") (pintype "bidirectional"))
      (node (ref "D3") (pin "1") (pinfunction "11_1") (pintype "passive"))
      (node (ref "Q5") (pin "P$S") (pinfunction "S_P$S") (pintype "passive"))
      (node (ref "R31") (pin "2") (pinfunction "2_2") (pintype "passive"))
      (node (ref "R82") (pin "1") (pinfunction "1_1") (pintype "passive"))
    )
    (net (code "11") (name "CELL10") (class "Default")
      (node (ref "CN1") (pin "P$3") (pinfunction "3_P$3") (pintype "bidirectional"))
      (node (ref "D2") (pin "1") (pinfunction "11_1") (pintype "passive"))
      (node (ref "Q4") (pin "P$S") (pinfunction "S_P$S") (pintype "passive"))
      (node (ref "R32") (pin "2") (pinfunction "2_2") (pintype "passive"))
      (node (ref "R79") (pin "1") (pinfunction "1_1") (pintype "passive"))
    )
    (net (code "12") (name "CELL11") (class "Default")
      (node (ref "CN1") (pin "P$2") (pinfunction "2_P$2") (pintype "bidirectional"))
      (node (ref "D1") (pin "1") (pinfunction "11_1") (pintype "passive"))
      (node (ref "Q3") (pin "P$S") (pinfunction "S_P$S") (pintype "passive"))
      (node (ref "R33") (pin "2") (pinfunction "2_2") (pintype "passive"))
      (node (ref "R62") (pin "1") (pinfunction "1_1") (pintype "passive"))
    )
    (net (code "13") (name "CELL12") (class "Default")
      (node (ref "CN1") (pin "P$1") (pinfunction "1_P$1") (pintype "bidirectional"))
      (node (ref "Q2") (pin "P$S") (pinfunction "S_P$S") (pintype "passive"))
      (node (ref "R34") (pin "2") (pinfunction "2_2") (pintype "passive"))
      (node (ref "R35") (pin "2") (pinfunction "2_2") (pintype "passive"))
    )
    (net (code "14") (name "CLK") (class "Default")
      (node (ref "R6") (pin "1") (pinfunction "1_1") (pintype "passive"))
      (node (ref "TP11") (pin "P$1") (pinfunction "P$1_P$1") (pintype "bidirectional"))
      (node (ref "U1") (pin "42") (pinfunction "SCK(IPA)_42") (pintype "passive"))
      (node (ref "U5") (pin "41") (pinfunction "RD3_41") (pintype "bidirectional"))
    )
    (net (code "15") (name "CS_1") (class "Default")
      (node (ref "R5") (pin "1") (pinfunction "1_1") (pintype "passive"))
      (node (ref "U1") (pin "41") (pinfunction "CSB(IMA)_41") (pintype "passive"))
      (node (ref "U5") (pin "37") (pinfunction "RC3_37") (pintype "bidirectional"))
    )
    (net (code "16") (name "C_SENSE") (class "Default")
      (node (ref "C5") (pin "1") (pinfunction "1_1") (pintype "passive"))
      (node (ref "R23") (pin "1") (pinfunction "1_1") (pintype "passive"))
      (node (ref "R69") (pin "2") (pinfunction "2_2") (pintype "passive"))
      (node (ref "TP3") (pin "P$1") (pinfunction "P$1_P$1") (pintype "bidirectional"))
      (node (ref "U7") (pin "7") (pinfunction "VOUT_7") (pintype "bidirectional"))
    )
    (net (code "17") (name "GND") (class "Default")
      (node (ref "C1") (pin "2") (pinfunction "2_2") (pintype "passive"))
      (node (ref "C10") (pin "2") (pinfunction "2_2") (pintype "passive"))
      (node (ref "C11") (pin "2") (pinfunction "2_2") (pintype "passive"))
      (node (ref "C12") (pin "2") (pinfunction "2_2") (pintype "passive"))
      (node (ref "C2") (pin "2") (pinfunction "2_2") (pintype "passive"))
      (node (ref "C25") (pin "2") (pinfunction "2_2") (pintype "passive"))
      (node (ref "C26") (pin "2") (pinfunction "22_2") (pintype "passive"))
      (node (ref "C3") (pin "2") (pinfunction "22_2") (pintype "passive"))
      (node (ref "C4") (pin "2") (pinfunction "2_2") (pintype "passive"))
      (node (ref "C5") (pin "2") (pinfunction "2_2") (pintype "passive"))
      (node (ref "C6") (pin "2") (pinfunction "2_2") (pintype "passive"))
      (node (ref "C7") (pin "2") (pinfunction "2_2") (pintype "passive"))
      (node (ref "C8") (pin "2") (pinfunction "2_2") (pintype "passive"))
      (node (ref "C9") (pin "2") (pinfunction "2_2") (pintype "passive"))
      (node (ref "CN2") (pin "P$3") (pinfunction "P$2_P$3") (pintype "bidirectional"))
      (node (ref "CN2") (pin "P$4") (pinfunction "P$2_P$4") (pintype "bidirectional"))
      (node (ref "CN3") (pin "P$14") (pinfunction "14_P$14") (pintype "bidirectional"))
      (node (ref "CN4") (pin "P$1") (pinfunction "P$1_P$1") (pintype "bidirectional"))
      (node (ref "CN4") (pin "P$2") (pinfunction "P$1_P$2") (pintype "bidirectional"))
      (node (ref "D12") (pin "1") (pinfunction "11_1") (pintype "passive"))
      (node (ref "D17") (pin "1") (pinfunction "1_1") (pintype "bidirectional"))
      (node (ref "J1") (pin "5") (pinfunction "5_5") (pintype "passive"))
      (node (ref "J2") (pin "2") (pinfunction "2_2") (pintype "passive"))
      (node (ref "J3") (pin "3") (pinfunction "3_3") (pintype "passive"))
      (node (ref "Q14") (pin "2") (pinfunction "S_2") (pintype "passive"))
      (node (ref "Q16") (pin "2") (pinfunction "S_2") (pintype "passive"))
      (node (ref "R1") (pin "1") (pinfunction "1_1") (pintype "passive"))
      (node (ref "R122") (pin "1") (pinfunction "1_1") (pintype "passive"))
      (node (ref "R4") (pin "1") (pinfunction "1_1") (pintype "passive"))
      (node (ref "R68") (pin "1") (pinfunction "1_1") (pintype "passive"))
      (node (ref "R70") (pin "1") (pinfunction "1_1") (pintype "passive"))
      (node (ref "R9") (pin "1") (pinfunction "1_1") (pintype "passive"))
      (node (ref "S2") (pin "P$3") (pinfunction "2_P$3") (pintype "bidirectional"))
      (node (ref "S2") (pin "P$4") (pinfunction "2_P$4") (pintype "bidirectional"))
      (node (ref "TP5") (pin "P$1") (pinfunction "P$1_P$1") (pintype "bidirectional"))
      (node (ref "U1") (pin "26") (pinfunction "C0_26") (pintype "passive"))
      (node (ref "U1") (pin "30") (pinfunction "V-_2_30") (pintype "power_in"))
      (node (ref "U1") (pin "31") (pinfunction "V-_31") (pintype "power_in"))
      (node (ref "U1") (pin "40") (pinfunction "ISOMD_40") (pintype "passive"))
      (node (ref "U1") (pin "45") (pinfunction "A0_45") (pintype "passive"))
      (node (ref "U1") (pin "46") (pinfunction "A1_46") (pintype "passive"))
      (node (ref "U1") (pin "47") (pinfunction "A2_47") (pintype "passive"))
      (node (ref "U1") (pin "48") (pinfunction "A3_48") (pintype "passive"))
      (node (ref "U3") (pin "2") (pinfunction "GND_2") (pintype "bidirectional"))
      (node (ref "U5") (pin "29") (pinfunction "VSS_29") (pintype "power_in"))
      (node (ref "U5") (pin "6") (pinfunction "VSS_6") (pintype "power_in"))
      (node (ref "U7") (pin "5") (pinfunction "VSS_5") (pintype "bidirectional"))
      (node (ref "U7") (pin "6") (pinfunction "MUST_6") (pintype "bidirectional"))
    )
    (net (code "18") (name "GPIO_1") (class "Default")
      (node (ref "CN3") (pin "P$8") (pinfunction "8_P$8") (pintype "bidirectional"))
      (node (ref "R64") (pin "2") (pinfunction "2_2") (pintype "passive"))
      (node (ref "R70") (pin "2") (pinfunction "2_2") (pintype "passive"))
    )
    (net (code "19") (name "GPIO_2") (class "Default")
      (node (ref "CN3") (pin "P$9") (pinfunction "9_P$9") (pintype "bidirectional"))
      (node (ref "R60") (pin "2") (pinfunction "2_2") (pintype "passive"))
    )
    (net (code "20") (name "GPIO_3") (class "Default")
      (node (ref "CN3") (pin "P$10") (pinfunction "10_P$10") (pintype "bidirectional"))
      (node (ref "R63") (pin "2") (pinfunction "2_2") (pintype "passive"))
    )
    (net (code "21") (name "GPIO_4") (class "Default")
      (node (ref "CN3") (pin "P$11") (pinfunction "11_P$11") (pintype "bidirectional"))
      (node (ref "R61") (pin "2") (pinfunction "2_2") (pintype "passive"))
    )
    (net (code "22") (name "GPIO_5") (class "Default")
      (node (ref "CN3") (pin "P$12") (pinfunction "12_P$12") (pintype "bidirectional"))
      (node (ref "R67") (pin "1") (pinfunction "1_1") (pintype "passive"))
    )
    (net (code "23") (name "I2C_CLK") (class "Default")
      (node (ref "CN3") (pin "P$6") (pinfunction "6_P$6") (pintype "bidirectional"))
      (node (ref "J2") (pin "5") (pinfunction "5_5") (pintype "passive"))
      (node (ref "J3") (pin "5") (pinfunction "5_5") (pintype "passive"))
      (node (ref "TP8") (pin "P$1") (pinfunction "P$1_P$1") (pintype "bidirectional"))
      (node (ref "U5") (pin "16") (pinfunction "ICSPCLK/RB6_16") (pintype "bidirectional"))
    )
    (net (code "24") (name "I2C_DATA") (class "Default")
      (node (ref "CN3") (pin "P$7") (pinfunction "7_P$7") (pintype "bidirectional"))
      (node (ref "J2") (pin "4") (pinfunction "4_4") (pintype "passive"))
      (node (ref "J3") (pin "4") (pinfunction "4_4") (pintype "passive"))
      (node (ref "TP7") (pin "P$1") (pinfunction "P$1_P$1") (pintype "bidirectional"))
      (node (ref "U5") (pin "17") (pinfunction "ICSPDAT/RB7_17") (pintype "bidirectional"))
    )
    (net (code "25") (name "MISO") (class "Default")
      (node (ref "R66") (pin "1") (pinfunction "1_1") (pintype "passive"))
      (node (ref "R7") (pin "1") (pinfunction "1_1") (pintype "passive"))
      (node (ref "TP10") (pin "P$1") (pinfunction "P$1_P$1") (pintype "bidirectional"))
      (node (ref "U1") (pin "44") (pinfunction "SDO(IBIAS)_44") (pintype "passive"))
      (node (ref "U5") (pin "42") (pinfunction "RC4_42") (pintype "bidirectional"))
    )
    (net (code "26") (name "MOSI") (class "Default")
      (node (ref "R65") (pin "1") (pinfunction "1_1") (pintype "passive"))
      (node (ref "R8") (pin "1") (pinfunction "1_1") (pintype "passive"))
      (node (ref "TP9") (pin "P$1") (pinfunction "P$1_P$1") (pintype "bidirectional"))
      (node (ref "U1") (pin "43") (pinfunction "SDI(ICMP)_43") (pintype "passive"))
      (node (ref "U5") (pin "43") (pinfunction "RC5_43") (pintype "bidirectional"))
    )
    (net (code "27") (name "Net-(C26-11)") (class "Default")
      (node (ref "C26") (pin "1") (pinfunction "11_1") (pintype "passive"))
      (node (ref "D17") (pin "3") (pinfunction "3_3") (pintype "bidirectional"))
      (node (ref "F1") (pin "2") (pinfunction "2_2") (pintype "passive"))
      (node (ref "U3") (pin "1") (pinfunction "VIN_1") (pintype "bidirectional"))
    )
    (net (code "28") (name "Net-(D1-22)") (class "Default")
      (node (ref "D1") (pin "2") (pinfunction "22_2") (pintype "passive"))
      (node (ref "R59") (pin "1") (pinfunction "1_1") (pintype "passive"))
    )
    (net (code "29") (name "Net-(D2-22)") (class "Default")
      (node (ref "D2") (pin "2") (pinfunction "22_2") (pintype "passive"))
      (node (ref "R58") (pin "1") (pinfunction "1_1") (pintype "passive"))
    )
    (net (code "30") (name "Net-(D3-22)") (class "Default")
      (node (ref "D3") (pin "2") (pinfunction "22_2") (pintype "passive"))
      (node (ref "R57") (pin "1") (pinfunction "1_1") (pintype "passive"))
    )
    (net (code "31") (name "Net-(D4-22)") (class "Default")
      (node (ref "D4") (pin "2") (pinfunction "22_2") (pintype "passive"))
      (node (ref "R56") (pin "1") (pinfunction "1_1") (pintype "passive"))
    )
    (net (code "32") (name "Net-(D5-22)") (class "Default")
      (node (ref "D5") (pin "2") (pinfunction "22_2") (pintype "passive"))
      (node (ref "R55") (pin "1") (pinfunction "1_1") (pintype "passive"))
    )
    (net (code "33") (name "Net-(D6-22)") (class "Default")
      (node (ref "D6") (pin "2") (pinfunction "22_2") (pintype "passive"))
      (node (ref "R54") (pin "1") (pinfunction "1_1") (pintype "passive"))
    )
    (net (code "34") (name "Net-(D7-22)") (class "Default")
      (node (ref "D7") (pin "2") (pinfunction "22_2") (pintype "passive"))
      (node (ref "R53") (pin "1") (pinfunction "1_1") (pintype "passive"))
    )
    (net (code "35") (name "Net-(D8-22)") (class "Default")
      (node (ref "D8") (pin "2") (pinfunction "22_2") (pintype "passive"))
      (node (ref "R52") (pin "1") (pinfunction "1_1") (pintype "passive"))
    )
    (net (code "36") (name "Net-(D9-22)") (class "Default")
      (node (ref "D9") (pin "2") (pinfunction "22_2") (pintype "passive"))
      (node (ref "R51") (pin "1") (pinfunction "1_1") (pintype "passive"))
    )
    (net (code "37") (name "Net-(D10-22)") (class "Default")
      (node (ref "D10") (pin "2") (pinfunction "22_2") (pintype "passive"))
      (node (ref "R50") (pin "1") (pinfunction "1_1") (pintype "passive"))
    )
    (net (code "38") (name "Net-(D11-22)") (class "Default")
      (node (ref "D11") (pin "2") (pinfunction "22_2") (pintype "passive"))
      (node (ref "R49") (pin "1") (pinfunction "1_1") (pintype "passive"))
    )
    (net (code "39") (name "Net-(D12-22)") (class "Default")
      (node (ref "D12") (pin "2") (pinfunction "22_2") (pintype "passive"))
      (node (ref "R48") (pin "1") (pinfunction "1_1") (pintype "passive"))
    )
    (net (code "40") (name "Net-(D13-11)") (class "Default")
      (node (ref "D13") (pin "1") (pinfunction "11_1") (pintype "passive"))
      (node (ref "R9") (pin "2") (pinfunction "2_2") (pintype "passive"))
    )
    (net (code "41") (name "Net-(D13-22)") (class "Default")
      (node (ref "D13") (pin "2") (pinfunction "22_2") (pintype "passive"))
      (node (ref "U5") (pin "24") (pinfunction "RA5_24") (pintype "bidirectional"))
    )
    (net (code "42") (name "Net-(D14-11)") (class "Default")
      (node (ref "D14") (pin "1") (pinfunction "11_1") (pintype "passive"))
      (node (ref "R7") (pin "2") (pinfunction "2_2") (pintype "passive"))
    )
    (net (code "43") (name "Net-(D15-11)") (class "Default")
      (node (ref "D15") (pin "1") (pinfunction "11_1") (pintype "passive"))
      (node (ref "R5") (pin "2") (pinfunction "2_2") (pintype "passive"))
    )
    (net (code "44") (name "Net-(D16-11)") (class "Default")
      (node (ref "D16") (pin "1") (pinfunction "11_1") (pintype "passive"))
      (node (ref "R8") (pin "2") (pinfunction "2_2") (pintype "passive"))
    )
    (net (code "45") (name "Net-(D18-11)") (class "Default")
      (node (ref "D18") (pin "1") (pinfunction "11_1") (pintype "passive"))
      (node (ref "R68") (pin "2") (pinfunction "2_2") (pintype "passive"))
    )
    (net (code "46") (name "Net-(Q1-D)") (class "Default")
      (node (ref "Q1") (pin "P$D") (pinfunction "D_P$D") (pintype "passive"))
      (node (ref "R122") (pin "2") (pinfunction "2_2") (pintype "passive"))
      (node (ref "R48") (pin "2") (pinfunction "2_2") (pintype "passive"))
    )
    (net (code "47") (name "Net-(Q1-G)") (class "Default")
      (node (ref "Q1") (pin "P$G") (pinfunction "G_P$G") (pintype "passive"))
      (node (ref "R36") (pin "2") (pinfunction "2_2") (pintype "passive"))
    )
    (net (code "48") (name "Net-(Q2-D)") (class "Default")
      (node (ref "Q2") (pin "P$D") (pinfunction "D_P$D") (pintype "passive"))
      (node (ref "R59") (pin "2") (pinfunction "2_2") (pintype "passive"))
      (node (ref "R62") (pin "2") (pinfunction "2_2") (pintype "passive"))
    )
    (net (code "49") (name "Net-(Q2-G)") (class "Default")
      (node (ref "Q2") (pin "P$G") (pinfunction "G_P$G") (pintype "passive"))
      (node (ref "R47") (pin "2") (pinfunction "2_2") (pintype "passive"))
    )
    (net (code "50") (name "Net-(Q3-D)") (class "Default")
      (node (ref "Q3") (pin "P$D") (pinfunction "D_P$D") (pintype "passive"))
      (node (ref "R58") (pin "2") (pinfunction "2_2") (pintype "passive"))
      (node (ref "R79") (pin "2") (pinfunction "2_2") (pintype "passive"))
    )
    (net (code "51") (name "Net-(Q3-G)") (class "Default")
      (node (ref "Q3") (pin "P$G") (pinfunction "G_P$G") (pintype "passive"))
      (node (ref "R46") (pin "2") (pinfunction "2_2") (pintype "passive"))
    )
    (net (code "52") (name "Net-(Q4-D)") (class "Default")
      (node (ref "Q4") (pin "P$D") (pinfunction "D_P$D") (pintype "passive"))
      (node (ref "R57") (pin "2") (pinfunction "2_2") (pintype "passive"))
      (node (ref "R82") (pin "2") (pinfunction "2_2") (pintype "passive"))
    )
    (net (code "53") (name "Net-(Q4-G)") (class "Default")
      (node (ref "Q4") (pin "P$G") (pinfunction "G_P$G") (pintype "passive"))
      (node (ref "R45") (pin "2") (pinfunction "2_2") (pintype "passive"))
    )
    (net (code "54") (name "Net-(Q5-D)") (class "Default")
      (node (ref "Q5") (pin "P$D") (pinfunction "D_P$D") (pintype "passive"))
      (node (ref "R56") (pin "2") (pinfunction "2_2") (pintype "passive"))
      (node (ref "R86") (pin "2") (pinfunction "2_2") (pintype "passive"))
    )
    (net (code "55") (name "Net-(Q5-G)") (class "Default")
      (node (ref "Q5") (pin "P$G") (pinfunction "G_P$G") (pintype "passive"))
      (node (ref "R44") (pin "2") (pinfunction "2_2") (pintype "passive"))
    )
    (net (code "56") (name "Net-(Q6-D)") (class "Default")
      (node (ref "Q6") (pin "P$D") (pinfunction "D_P$D") (pintype "passive"))
      (node (ref "R55") (pin "2") (pinfunction "2_2") (pintype "passive"))
      (node (ref "R90") (pin "2") (pinfunction "2_2") (pintype "passive"))
    )
    (net (code "57") (name "Net-(Q6-G)") (class "Default")
      (node (ref "Q6") (pin "P$G") (pinfunction "G_P$G") (pintype "passive"))
      (node (ref "R43") (pin "2") (pinfunction "2_2") (pintype "passive"))
    )
    (net (code "58") (name "Net-(Q7-D)") (class "Default")
      (node (ref "Q7") (pin "P$D") (pinfunction "D_P$D") (pintype "passive"))
      (node (ref "R54") (pin "2") (pinfunction "2_2") (pintype "passive"))
      (node (ref "R94") (pin "2") (pinfunction "2_2") (pintype "passive"))
    )
    (net (code "59") (name "Net-(Q7-G)") (class "Default")
      (node (ref "Q7") (pin "P$G") (pinfunction "G_P$G") (pintype "passive"))
      (node (ref "R42") (pin "2") (pinfunction "2_2") (pintype "passive"))
    )
    (net (code "60") (name "Net-(Q8-D)") (class "Default")
      (node (ref "Q8") (pin "P$D") (pinfunction "D_P$D") (pintype "passive"))
      (node (ref "R53") (pin "2") (pinfunction "2_2") (pintype "passive"))
      (node (ref "R98") (pin "2") (pinfunction "2_2") (pintype "passive"))
    )
    (net (code "61") (name "Net-(Q8-G)") (class "Default")
      (node (ref "Q8") (pin "P$G") (pinfunction "G_P$G") (pintype "passive"))
      (node (ref "R41") (pin "2") (pinfunction "2_2") (pintype "passive"))
    )
    (net (code "62") (name "Net-(Q9-D)") (class "Default")
      (node (ref "Q9") (pin "P$D") (pinfunction "D_P$D") (pintype "passive"))
      (node (ref "R102") (pin "2") (pinfunction "2_2") (pintype "passive"))
      (node (ref "R52") (pin "2") (pinfunction "2_2") (pintype "passive"))
    )
    (net (code "63") (name "Net-(Q9-G)") (class "Default")
      (node (ref "Q9") (pin "P$G") (pinfunction "G_P$G") (pintype "passive"))
      (node (ref "R40") (pin "2") (pinfunction "2_2") (pintype "passive"))
    )
    (net (code "64") (name "Net-(Q10-D)") (class "Default")
      (node (ref "Q10") (pin "P$D") (pinfunction "D_P$D") (pintype "passive"))
      (node (ref "R106") (pin "2") (pinfunction "2_2") (pintype "passive"))
      (node (ref "R51") (pin "2") (pinfunction "2_2") (pintype "passive"))
    )
    (net (code "65") (name "Net-(Q10-G)") (class "Default")
      (node (ref "Q10") (pin "P$G") (pinfunction "G_P$G") (pintype "passive"))
      (node (ref "R39") (pin "2") (pinfunction "2_2") (pintype "passive"))
    )
    (net (code "66") (name "Net-(Q11-D)") (class "Default")
      (node (ref "Q11") (pin "P$D") (pinfunction "D_P$D") (pintype "passive"))
      (node (ref "R110") (pin "2") (pinfunction "2_2") (pintype "passive"))
      (node (ref "R50") (pin "2") (pinfunction "2_2") (pintype "passive"))
    )
    (net (code "67") (name "Net-(Q11-G)") (class "Default")
      (node (ref "Q11") (pin "P$G") (pinfunction "G_P$G") (pintype "passive"))
      (node (ref "R38") (pin "2") (pinfunction "2_2") (pintype "passive"))
    )
    (net (code "68") (name "Net-(Q12-D)") (class "Default")
      (node (ref "Q12") (pin "P$D") (pinfunction "D_P$D") (pintype "passive"))
      (node (ref "R118") (pin "2") (pinfunction "2_2") (pintype "passive"))
      (node (ref "R49") (pin "2") (pinfunction "2_2") (pintype "passive"))
    )
    (net (code "69") (name "Net-(Q12-G)") (class "Default")
      (node (ref "Q12") (pin "P$G") (pinfunction "G_P$G") (pintype "passive"))
      (node (ref "R37") (pin "2") (pinfunction "2_2") (pintype "passive"))
    )
    (net (code "70") (name "Net-(Q13-D)") (class "Default")
      (node (ref "Q13") (pin "3") (pinfunction "D_3") (pintype "passive"))
      (node (ref "R16") (pin "2") (pinfunction "2_2") (pintype "passive"))
      (node (ref "R17") (pin "2") (pinfunction "2_2") (pintype "passive"))
      (node (ref "R18") (pin "2") (pinfunction "2_2") (pintype "passive"))
      (node (ref "R19") (pin "2") (pinfunction "2_2") (pintype "passive"))
      (node (ref "R20") (pin "2") (pinfunction "2_2") (pintype "passive"))
      (node (ref "TP6") (pin "P$1") (pinfunction "P$1_P$1") (pintype "bidirectional"))
    )
    (net (code "71") (name "Net-(Q13-G)") (class "Default")
      (node (ref "Q13") (pin "1") (pinfunction "G_1") (pintype "passive"))
      (node (ref "R21") (pin "1") (pinfunction "1_1") (pintype "passive"))
      (node (ref "R22") (pin "2") (pinfunction "2_2") (pintype "passive"))
    )
    (net (code "72") (name "Net-(Q14-D)") (class "Default")
      (node (ref "Q14") (pin "3") (pinfunction "D_3") (pintype "passive"))
      (node (ref "R12") (pin "1") (pinfunction "1_1") (pintype "passive"))
    )
    (net (code "73") (name "Net-(Q14-G)") (class "Default")
      (node (ref "Q14") (pin "1") (pinfunction "G_1") (pintype "passive"))
      (node (ref "R14") (pin "1") (pinfunction "1_1") (pintype "passive"))
      (node (ref "R4") (pin "2") (pinfunction "2_2") (pintype "passive"))
    )
    (net (code "74") (name "Net-(Q15-G)") (class "Default")
      (node (ref "Q15") (pin "1") (pinfunction "G_1") (pintype "passive"))
      (node (ref "R11") (pin "1") (pinfunction "1_1") (pintype "passive"))
      (node (ref "R12") (pin "2") (pinfunction "2_2") (pintype "passive"))
    )
    (net (code "75") (name "Net-(Q16-D)") (class "Default")
      (node (ref "Q16") (pin "3") (pinfunction "D_3") (pintype "passive"))
      (node (ref "R13") (pin "1") (pinfunction "1_1") (pintype "passive"))
    )
    (net (code "76") (name "Net-(Q16-G)") (class "Default")
      (node (ref "Q16") (pin "1") (pinfunction "G_1") (pintype "passive"))
      (node (ref "R1") (pin "2") (pinfunction "2_2") (pintype "passive"))
      (node (ref "R15") (pin "1") (pinfunction "1_1") (pintype "passive"))
    )
    (net (code "77") (name "Net-(Q17-G)") (class "Default")
      (node (ref "Q17") (pin "1") (pinfunction "G_1") (pintype "passive"))
      (node (ref "R13") (pin "2") (pinfunction "2_2") (pintype "passive"))
      (node (ref "R3") (pin "1") (pinfunction "1_1") (pintype "passive"))
    )
    (net (code "78") (name "Net-(U1-C1)") (class "Default")
      (node (ref "C24") (pin "2") (pinfunction "2_2") (pintype "passive"))
      (node (ref "C25") (pin "1") (pinfunction "1_1") (pintype "passive"))
      (node (ref "R2") (pin "1") (pinfunction "1_1") (pintype "passive"))
      (node (ref "U1") (pin "24") (pinfunction "C1_24") (pintype "passive"))
    )
    (net (code "79") (name "Net-(U1-C2)") (class "Default")
      (node (ref "C23") (pin "2") (pinfunction "2_2") (pintype "passive"))
      (node (ref "C24") (pin "1") (pinfunction "1_1") (pintype "passive"))
      (node (ref "R24") (pin "1") (pinfunction "1_1") (pintype "passive"))
      (node (ref "U1") (pin "22") (pinfunction "C2_22") (pintype "passive"))
    )
    (net (code "80") (name "Net-(U1-C3)") (class "Default")
      (node (ref "C22") (pin "2") (pinfunction "2_2") (pintype "passive"))
      (node (ref "C23") (pin "1") (pinfunction "1_1") (pintype "passive"))
      (node (ref "R25") (pin "1") (pinfunction "1_1") (pintype "passive"))
      (node (ref "U1") (pin "20") (pinfunction "C3_20") (pintype "passive"))
    )
    (net (code "81") (name "Net-(U1-C4)") (class "Default")
      (node (ref "C21") (pin "2") (pinfunction "2_2") (pintype "passive"))
      (node (ref "C22") (pin "1") (pinfunction "1_1") (pintype "passive"))
      (node (ref "R26") (pin "1") (pinfunction "1_1") (pintype "passive"))
      (node (ref "U1") (pin "18") (pinfunction "C4_18") (pintype "passive"))
    )
    (net (code "82") (name "Net-(U1-C5)") (class "Default")
      (node (ref "C20") (pin "2") (pinfunction "2_2") (pintype "passive"))
      (node (ref "C21") (pin "1") (pinfunction "1_1") (pintype "passive"))
      (node (ref "R27") (pin "1") (pinfunction "1_1") (pintype "passive"))
      (node (ref "U1") (pin "16") (pinfunction "C5_16") (pintype "passive"))
    )
    (net (code "83") (name "Net-(U1-C6)") (class "Default")
      (node (ref "C19") (pin "2") (pinfunction "2_2") (pintype "passive"))
      (node (ref "C20") (pin "1") (pinfunction "1_1") (pintype "passive"))
      (node (ref "R28") (pin "1") (pinfunction "1_1") (pintype "passive"))
      (node (ref "U1") (pin "14") (pinfunction "C6_14") (pintype "passive"))
    )
    (net (code "84") (name "Net-(U1-C7)") (class "Default")
      (node (ref "C18") (pin "2") (pinfunction "2_2") (pintype "passive"))
      (node (ref "C19") (pin "1") (pinfunction "1_1") (pintype "passive"))
      (node (ref "R29") (pin "1") (pinfunction "1_1") (pintype "passive"))
      (node (ref "U1") (pin "12") (pinfunction "C7_12") (pintype "passive"))
    )
    (net (code "85") (name "Net-(U1-C8)") (class "Default")
      (node (ref "C17") (pin "2") (pinfunction "2_2") (pintype "passive"))
      (node (ref "C18") (pin "1") (pinfunction "1_1") (pintype "passive"))
      (node (ref "R30") (pin "1") (pinfunction "1_1") (pintype "passive"))
      (node (ref "U1") (pin "10") (pinfunction "C8_10") (pintype "passive"))
    )
    (net (code "86") (name "Net-(U1-C9)") (class "Default")
      (node (ref "C16") (pin "2") (pinfunction "2_2") (pintype "passive"))
      (node (ref "C17") (pin "1") (pinfunction "1_1") (pintype "passive"))
      (node (ref "R31") (pin "1") (pinfunction "1_1") (pintype "passive"))
      (node (ref "U1") (pin "8") (pinfunction "C9_8") (pintype "passive"))
    )
    (net (code "87") (name "Net-(U1-C10)") (class "Default")
      (node (ref "C13") (pin "2") (pinfunction "2_2") (pintype "passive"))
      (node (ref "C16") (pin "1") (pinfunction "1_1") (pintype "passive"))
      (node (ref "R32") (pin "1") (pinfunction "1_1") (pintype "passive"))
      (node (ref "U1") (pin "6") (pinfunction "C10_6") (pintype "passive"))
    )
    (net (code "88") (name "Net-(U1-C11)") (class "Default")
      (node (ref "C13") (pin "1") (pinfunction "1_1") (pintype "passive"))
      (node (ref "C14") (pin "2") (pinfunction "2_2") (pintype "passive"))
      (node (ref "R33") (pin "1") (pinfunction "1_1") (pintype "passive"))
      (node (ref "U1") (pin "4") (pinfunction "C11_4") (pintype "passive"))
    )
    (net (code "89") (name "Net-(U1-C12)") (class "Default")
      (node (ref "C14") (pin "1") (pinfunction "1_1") (pintype "passive"))
      (node (ref "R34") (pin "1") (pinfunction "1_1") (pintype "passive"))
      (node (ref "U1") (pin "2") (pinfunction "C12_2") (pintype "passive"))
    )
    (net (code "90") (name "Net-(U1-S1)") (class "Default")
      (node (ref "R36") (pin "1") (pinfunction "1_1") (pintype "passive"))
      (node (ref "U1") (pin "25") (pinfunction "S1_25") (pintype "passive"))
    )
    (net (code "91") (name "Net-(U1-S2)") (class "Default")
      (node (ref "R37") (pin "1") (pinfunction "1_1") (pintype "passive"))
      (node (ref "U1") (pin "23") (pinfunction "S2_23") (pintype "passive"))
    )
    (net (code "92") (name "Net-(U1-S3)") (class "Default")
      (node (ref "R38") (pin "1") (pinfunction "1_1") (pintype "passive"))
      (node (ref "U1") (pin "21") (pinfunction "S3_21") (pintype "passive"))
    )
    (net (code "93") (name "Net-(U1-S4)") (class "Default")
      (node (ref "R39") (pin "1") (pinfunction "1_1") (pintype "passive"))
      (node (ref "U1") (pin "19") (pinfunction "S4_19") (pintype "passive"))
    )
    (net (code "94") (name "Net-(U1-S5)") (class "Default")
      (node (ref "R40") (pin "1") (pinfunction "1_1") (pintype "passive"))
      (node (ref "U1") (pin "17") (pinfunction "S5_17") (pintype "passive"))
    )
    (net (code "95") (name "Net-(U1-S6)") (class "Default")
      (node (ref "R41") (pin "1") (pinfunction "1_1") (pintype "passive"))
      (node (ref "U1") (pin "15") (pinfunction "S6_15") (pintype "passive"))
    )
    (net (code "96") (name "Net-(U1-S7)") (class "Default")
      (node (ref "R42") (pin "1") (pinfunction "1_1") (pintype "passive"))
      (node (ref "U1") (pin "13") (pinfunction "S7_13") (pintype "passive"))
    )
    (net (code "97") (name "Net-(U1-S8)") (class "Default")
      (node (ref "R43") (pin "1") (pinfunction "1_1") (pintype "passive"))
      (node (ref "U1") (pin "11") (pinfunction "S8_11") (pintype "passive"))
    )
    (net (code "98") (name "Net-(U1-S9)") (class "Default")
      (node (ref "R44") (pin "1") (pinfunction "1_1") (pintype "passive"))
      (node (ref "U1") (pin "9") (pinfunction "S9_9") (pintype "passive"))
    )
    (net (code "99") (name "Net-(U1-S10)") (class "Default")
      (node (ref "R45") (pin "1") (pinfunction "1_1") (pintype "passive"))
      (node (ref "U1") (pin "7") (pinfunction "S10_7") (pintype "passive"))
    )
    (net (code "100") (name "Net-(U1-S11)") (class "Default")
      (node (ref "R46") (pin "1") (pinfunction "1_1") (pintype "passive"))
      (node (ref "U1") (pin "5") (pinfunction "S11_5") (pintype "passive"))
    )
    (net (code "101") (name "Net-(U1-S12)") (class "Default")
      (node (ref "R47") (pin "1") (pinfunction "1_1") (pintype "passive"))
      (node (ref "U1") (pin "3") (pinfunction "S12_3") (pintype "passive"))
    )
    (net (code "102") (name "Net-(U1-V+)") (class "Default")
      (node (ref "C4") (pin "1") (pinfunction "1_1") (pintype "passive"))
      (node (ref "R35") (pin "1") (pinfunction "1_1") (pintype "passive"))
      (node (ref "U1") (pin "1") (pinfunction "V+_1") (pintype "power_in"))
    )
    (net (code "103") (name "Net-(U1-VREF1)") (class "Default")
      (node (ref "C6") (pin "1") (pinfunction "1_1") (pintype "passive"))
      (node (ref "U1") (pin "35") (pinfunction "VREF1_35") (pintype "passive"))
    )
    (net (code "104") (name "Net-(U1-VREF2)") (class "Default")
      (node (ref "C2") (pin "1") (pinfunction "1_1") (pintype "passive"))
      (node (ref "U1") (pin "34") (pinfunction "VREF2_34") (pintype "passive"))
    )
    (net (code "105") (name "Net-(U5-RA0)") (class "Default")
      (node (ref "R64") (pin "1") (pinfunction "1_1") (pintype "passive"))
      (node (ref "U5") (pin "19") (pinfunction "RA0_19") (pintype "bidirectional"))
    )
    (net (code "106") (name "Net-(U5-RA1)") (class "Default")
      (node (ref "R60") (pin "1") (pinfunction "1_1") (pintype "passive"))
      (node (ref "U5") (pin "20") (pinfunction "RA1_20") (pintype "bidirectional"))
    )
    (net (code "107") (name "Net-(U5-RA2)") (class "Default")
      (node (ref "R63") (pin "1") (pinfunction "1_1") (pintype "passive"))
      (node (ref "U5") (pin "21") (pinfunction "RA2_21") (pintype "bidirectional"))
    )
    (net (code "108") (name "Net-(U5-RA3)") (class "Default")
      (node (ref "R61") (pin "1") (pinfunction "1_1") (pintype "passive"))
      (node (ref "U5") (pin "22") (pinfunction "RA3_22") (pintype "bidirectional"))
    )
    (net (code "109") (name "Net-(U5-RA4)") (class "Default")
      (node (ref "R67") (pin "2") (pinfunction "2_2") (pintype "passive"))
      (node (ref "U5") (pin "23") (pinfunction "RA4_23") (pintype "bidirectional"))
    )
    (net (code "110") (name "Net-(U5-RA6)") (class "Default")
      (node (ref "C11") (pin "1") (pinfunction "1_1") (pintype "passive"))
      (node (ref "U5") (pin "31") (pinfunction "RA6_31") (pintype "open_collector"))
      (node (ref "Y1") (pin "2") (pinfunction "2_2") (pintype "passive"))
    )
    (net (code "111") (name "Net-(U5-RA7)") (class "Default")
      (node (ref "C12") (pin "1") (pinfunction "1_1") (pintype "passive"))
      (node (ref "U5") (pin "30") (pinfunction "RA7_30") (pintype "bidirectional"))
      (node (ref "Y1") (pin "1") (pinfunction "1_1") (pintype "passive"))
    )
    (net (code "112") (name "Net-(U5-RD1)") (class "Default")
      (node (ref "C8") (pin "1") (pinfunction "1_1") (pintype "passive"))
      (node (ref "R69") (pin "1") (pinfunction "1_1") (pintype "passive"))
      (node (ref "U5") (pin "39") (pinfunction "RD1_39") (pintype "bidirectional"))
    )
    (net (code "113") (name "Net-(U5-VPP{slash}~{MCLR{slash}RE3})") (class "Default")
      (node (ref "J3") (pin "1") (pinfunction "1_1") (pintype "passive"))
      (node (ref "R10") (pin "1") (pinfunction "1_1") (pintype "passive"))
      (node (ref "S2") (pin "P$1") (pinfunction "1_P$1") (pintype "bidirectional"))
      (node (ref "S2") (pin "P$2") (pinfunction "1_P$2") (pintype "bidirectional"))
      (node (ref "U5") (pin "18") (pinfunction "VPP/~{MCLR/RE3}_18") (pintype "bidirectional"))
    )
    (net (code "114") (name "RX") (class "Default")
      (node (ref "J1") (pin "3") (pinfunction "3_3") (pintype "passive"))
      (node (ref "U5") (pin "1") (pinfunction "RC7_1") (pintype "bidirectional"))
    )
    (net (code "115") (name "TEMP1") (class "Default")
      (node (ref "CN3") (pin "P$1") (pinfunction "1_P$1") (pintype "bidirectional"))
      (node (ref "R16") (pin "1") (pinfunction "1_1") (pintype "passive"))
      (node (ref "TP16") (pin "P$1") (pinfunction "P$1_P$1") (pintype "bidirectional"))
      (node (ref "U5") (pin "8") (pinfunction "RB0_8") (pintype "bidirectional"))
    )
    (net (code "116") (name "TEMP2") (class "Default")
      (node (ref "CN3") (pin "P$2") (pinfunction "2_P$2") (pintype "bidirectional"))
      (node (ref "R17") (pin "1") (pinfunction "1_1") (pintype "passive"))
      (node (ref "TP15") (pin "P$1") (pinfunction "P$1_P$1") (pintype "bidirectional"))
      (node (ref "U5") (pin "9") (pinfunction "RB1_9") (pintype "bidirectional"))
    )
    (net (code "117") (name "TEMP3") (class "Default")
      (node (ref "CN3") (pin "P$3") (pinfunction "3_P$3") (pintype "bidirectional"))
      (node (ref "R18") (pin "1") (pinfunction "1_1") (pintype "passive"))
      (node (ref "TP14") (pin "P$1") (pinfunction "P$1_P$1") (pintype "bidirectional"))
      (node (ref "U5") (pin "10") (pinfunction "RB2_10") (pintype "bidirectional"))
    )
    (net (code "118") (name "TEMP4") (class "Default")
      (node (ref "CN3") (pin "P$4") (pinfunction "4_P$4") (pintype "bidirectional"))
      (node (ref "R19") (pin "1") (pinfunction "1_1") (pintype "passive"))
      (node (ref "TP13") (pin "P$1") (pinfunction "P$1_P$1") (pintype "bidirectional"))
      (node (ref "U5") (pin "11") (pinfunction "RB3_11") (pintype "bidirectional"))
    )
    (net (code "119") (name "TEMP5") (class "Default")
      (node (ref "CN3") (pin "P$5") (pinfunction "5_P$5") (pintype "bidirectional"))
      (node (ref "R20") (pin "1") (pinfunction "1_1") (pintype "passive"))
      (node (ref "TP12") (pin "P$1") (pinfunction "P$1_P$1") (pintype "bidirectional"))
      (node (ref "U5") (pin "14") (pinfunction "RB4_14") (pintype "bidirectional"))
    )
    (net (code "120") (name "TEMP_FET") (class "Default")
      (node (ref "R22") (pin "1") (pinfunction "1_1") (pintype "passive"))
      (node (ref "U5") (pin "15") (pinfunction "RB5_15") (pintype "bidirectional"))
    )
    (net (code "121") (name "TO_CHARGER_EN") (class "Default")
      (node (ref "R15") (pin "2") (pinfunction "2_2") (pintype "passive"))
      (node (ref "U5") (pin "2") (pinfunction "RD4_2") (pintype "bidirectional"))
    )
    (net (code "122") (name "TO_CHARGER{slash}MOTOR") (class "Default")
      (node (ref "CN4") (pin "P$3") (pinfunction "P$2_P$3") (pintype "bidirectional"))
      (node (ref "CN4") (pin "P$4") (pinfunction "P$2_P$4") (pintype "bidirectional"))
      (node (ref "Q15") (pin "2") (pinfunction "D_2") (pintype "passive"))
      (node (ref "Q17") (pin "3") (pinfunction "S_3") (pintype "passive"))
      (node (ref "R3") (pin "2") (pinfunction "2_2") (pintype "passive"))
    )
    (net (code "123") (name "TO_MOTOR_EN") (class "Default")
      (node (ref "R14") (pin "2") (pinfunction "2_2") (pintype "passive"))
      (node (ref "U5") (pin "3") (pinfunction "RD5_3") (pintype "bidirectional"))
    )
    (net (code "124") (name "TX") (class "Default")
      (node (ref "J1") (pin "2") (pinfunction "2_2") (pintype "passive"))
      (node (ref "U5") (pin "44") (pinfunction "RC6_44") (pintype "bidirectional"))
    )
    (net (code "125") (name "VCC") (class "Default")
      (node (ref "CN2") (pin "P$1") (pinfunction "P$1_P$1") (pintype "bidirectional"))
      (node (ref "CN2") (pin "P$2") (pinfunction "P$1_P$2") (pintype "bidirectional"))
      (node (ref "U7") (pin "1") (pinfunction "IP+_1") (pintype "bidirectional"))
      (node (ref "U7") (pin "2") (pinfunction "IP+_2") (pintype "bidirectional"))
    )
    (net (code "126") (name "VCC_1") (class "Default")
      (node (ref "F1") (pin "1") (pinfunction "1_1") (pintype "passive"))
      (node (ref "Q15") (pin "3") (pinfunction "S_3") (pintype "passive"))
      (node (ref "Q17") (pin "2") (pinfunction "D_2") (pintype "passive"))
      (node (ref "R11") (pin "2") (pinfunction "2_2") (pintype "passive"))
      (node (ref "TP4") (pin "P$1") (pinfunction "P$1_P$1") (pintype "bidirectional"))
      (node (ref "U7") (pin "3") (pinfunction "IP-_3") (pintype "bidirectional"))
      (node (ref "U7") (pin "4") (pinfunction "IP-_4") (pintype "bidirectional"))
    )
    (net (code "127") (name "unconnected-(CN1-13-PadP$13)") (class "Default")
      (node (ref "CN1") (pin "P$13") (pinfunction "13_P$13") (pintype "bidirectional"))
    )
    (net (code "128") (name "unconnected-(CN1-14-PadP$14)") (class "Default")
      (node (ref "CN1") (pin "P$14") (pinfunction "14_P$14") (pintype "bidirectional"))
    )
    (net (code "129") (name "unconnected-(CN1-15-PadP$15)") (class "Default")
      (node (ref "CN1") (pin "P$15") (pinfunction "15_P$15") (pintype "bidirectional"))
    )
    (net (code "130") (name "unconnected-(CN1-16-PadP$16)") (class "Default")
      (node (ref "CN1") (pin "P$16") (pinfunction "16_P$16") (pintype "bidirectional"))
    )
    (net (code "131") (name "unconnected-(CN3-15-PadP$15)") (class "Default")
      (node (ref "CN3") (pin "P$15") (pinfunction "15_P$15") (pintype "bidirectional"))
    )
    (net (code "132") (name "unconnected-(CN3-16-PadP$16)") (class "Default")
      (node (ref "CN3") (pin "P$16") (pinfunction "16_P$16") (pintype "bidirectional"))
    )
    (net (code "133") (name "unconnected-(J1-Pad1)") (class "Default")
      (node (ref "J1") (pin "1") (pinfunction "1_1") (pintype "passive"))
    )
    (net (code "134") (name "unconnected-(J1-Pad4)") (class "Default")
      (node (ref "J1") (pin "4") (pinfunction "4_4") (pintype "passive"))
    )
    (net (code "135") (name "unconnected-(J2-Pad1)") (class "Default")
      (node (ref "J2") (pin "1") (pinfunction "1_1") (pintype "passive"))
    )
    (net (code "136") (name "unconnected-(U1-DRIVE-Pad38)") (class "Default")
      (node (ref "U1") (pin "38") (pinfunction "DRIVE_38") (pintype "passive"))
    )
    (net (code "137") (name "unconnected-(U1-GPIO1-Pad27)") (class "Default")
      (node (ref "U1") (pin "27") (pinfunction "GPIO1_27") (pintype "bidirectional"))
    )
    (net (code "138") (name "unconnected-(U1-GPIO2-Pad28)") (class "Default")
      (node (ref "U1") (pin "28") (pinfunction "GPIO2_28") (pintype "bidirectional"))
    )
    (net (code "139") (name "unconnected-(U1-GPIO3-Pad29)") (class "Default")
      (node (ref "U1") (pin "29") (pinfunction "GPIO3_29") (pintype "bidirectional"))
    )
    (net (code "140") (name "unconnected-(U1-GPIO4-Pad32)") (class "Default")
      (node (ref "U1") (pin "32") (pinfunction "GPIO4_32") (pintype "bidirectional"))
    )
    (net (code "141") (name "unconnected-(U1-GPIO5-Pad33)") (class "Default")
      (node (ref "U1") (pin "33") (pinfunction "GPIO5_33") (pintype "bidirectional"))
    )
    (net (code "142") (name "unconnected-(U1-SWTEN-Pad36)") (class "Default")
      (node (ref "U1") (pin "36") (pinfunction "SWTEN_36") (pintype "passive"))
    )
    (net (code "143") (name "unconnected-(U1-WDT-Pad39)") (class "Default")
      (node (ref "U1") (pin "39") (pinfunction "WDT_39") (pintype "passive"))
    )
    (net (code "144") (name "unconnected-(U5-N.C.-Pad12)") (class "Default")
      (node (ref "U5") (pin "12") (pinfunction "N.C._12") (pintype "no_connect"))
    )
    (net (code "145") (name "unconnected-(U5-N.C.-Pad33)") (class "Default")
      (node (ref "U5") (pin "33") (pinfunction "N.C._33") (pintype "no_connect"))
    )
    (net (code "146") (name "unconnected-(U5-N.C.-Pad34)") (class "Default")
      (node (ref "U5") (pin "34") (pinfunction "N.C._34") (pintype "no_connect"))
    )
    (net (code "147") (name "unconnected-(U5-NC_2-Pad13)") (class "Default")
      (node (ref "U5") (pin "13") (pinfunction "NC_2_13") (pintype "no_connect"))
    )
    (net (code "148") (name "unconnected-(U5-RC0-Pad32)") (class "Default")
      (node (ref "U5") (pin "32") (pinfunction "RC0_32") (pintype "bidirectional"))
    )
    (net (code "149") (name "unconnected-(U5-RC1-Pad35)") (class "Default")
      (node (ref "U5") (pin "35") (pinfunction "RC1_35") (pintype "bidirectional"))
    )
    (net (code "150") (name "unconnected-(U5-RC2-Pad36)") (class "Default")
      (node (ref "U5") (pin "36") (pinfunction "RC2_36") (pintype "bidirectional"))
    )
    (net (code "151") (name "unconnected-(U5-RD0-Pad38)") (class "Default")
      (node (ref "U5") (pin "38") (pinfunction "RD0_38") (pintype "bidirectional"))
    )
    (net (code "152") (name "unconnected-(U5-RD2-Pad40)") (class "Default")
      (node (ref "U5") (pin "40") (pinfunction "RD2_40") (pintype "bidirectional"))
    )
    (net (code "153") (name "unconnected-(U5-RD6-Pad4)") (class "Default")
      (node (ref "U5") (pin "4") (pinfunction "RD6_4") (pintype "bidirectional"))
    )
    (net (code "154") (name "unconnected-(U5-RD7-Pad5)") (class "Default")
      (node (ref "U5") (pin "5") (pinfunction "RD7_5") (pintype "bidirectional"))
    )
    (net (code "155") (name "unconnected-(U5-RE0-Pad25)") (class "Default")
      (node (ref "U5") (pin "25") (pinfunction "RE0_25") (pintype "bidirectional"))
    )
    (net (code "156") (name "unconnected-(U5-RE1-Pad26)") (class "Default")
      (node (ref "U5") (pin "26") (pinfunction "RE1_26") (pintype "bidirectional"))
    )
    (net (code "157") (name "unconnected-(U5-RE2-Pad27)") (class "Default")
      (node (ref "U5") (pin "27") (pinfunction "RE2_27") (pintype "bidirectional"))
    )
  )
)
